# MSP-EXP430F5529_2_2.net
KiCad netlist of a schematic drawn in EAGLE
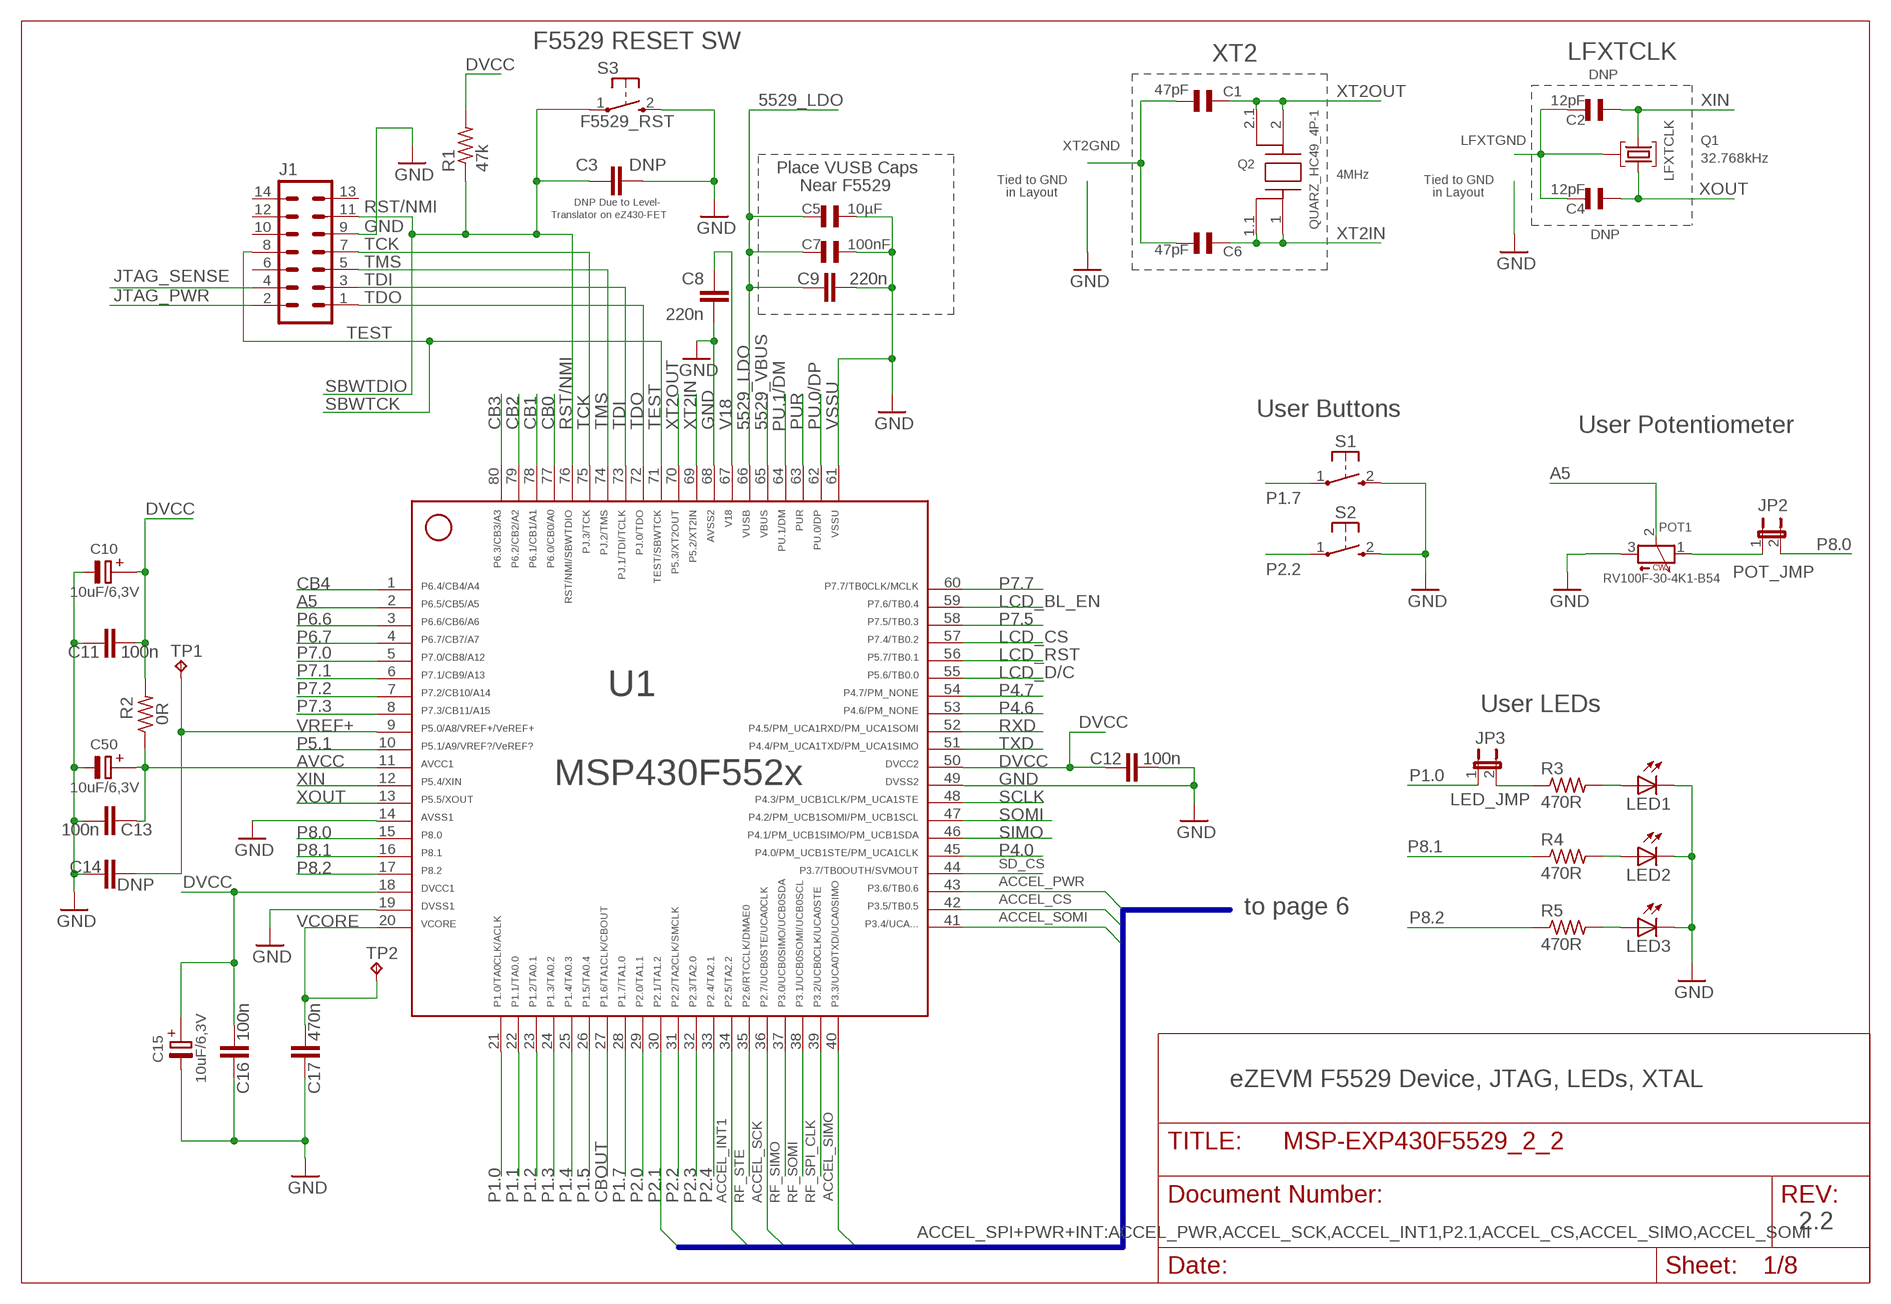
[diagram p0: schematic, sheet 1]
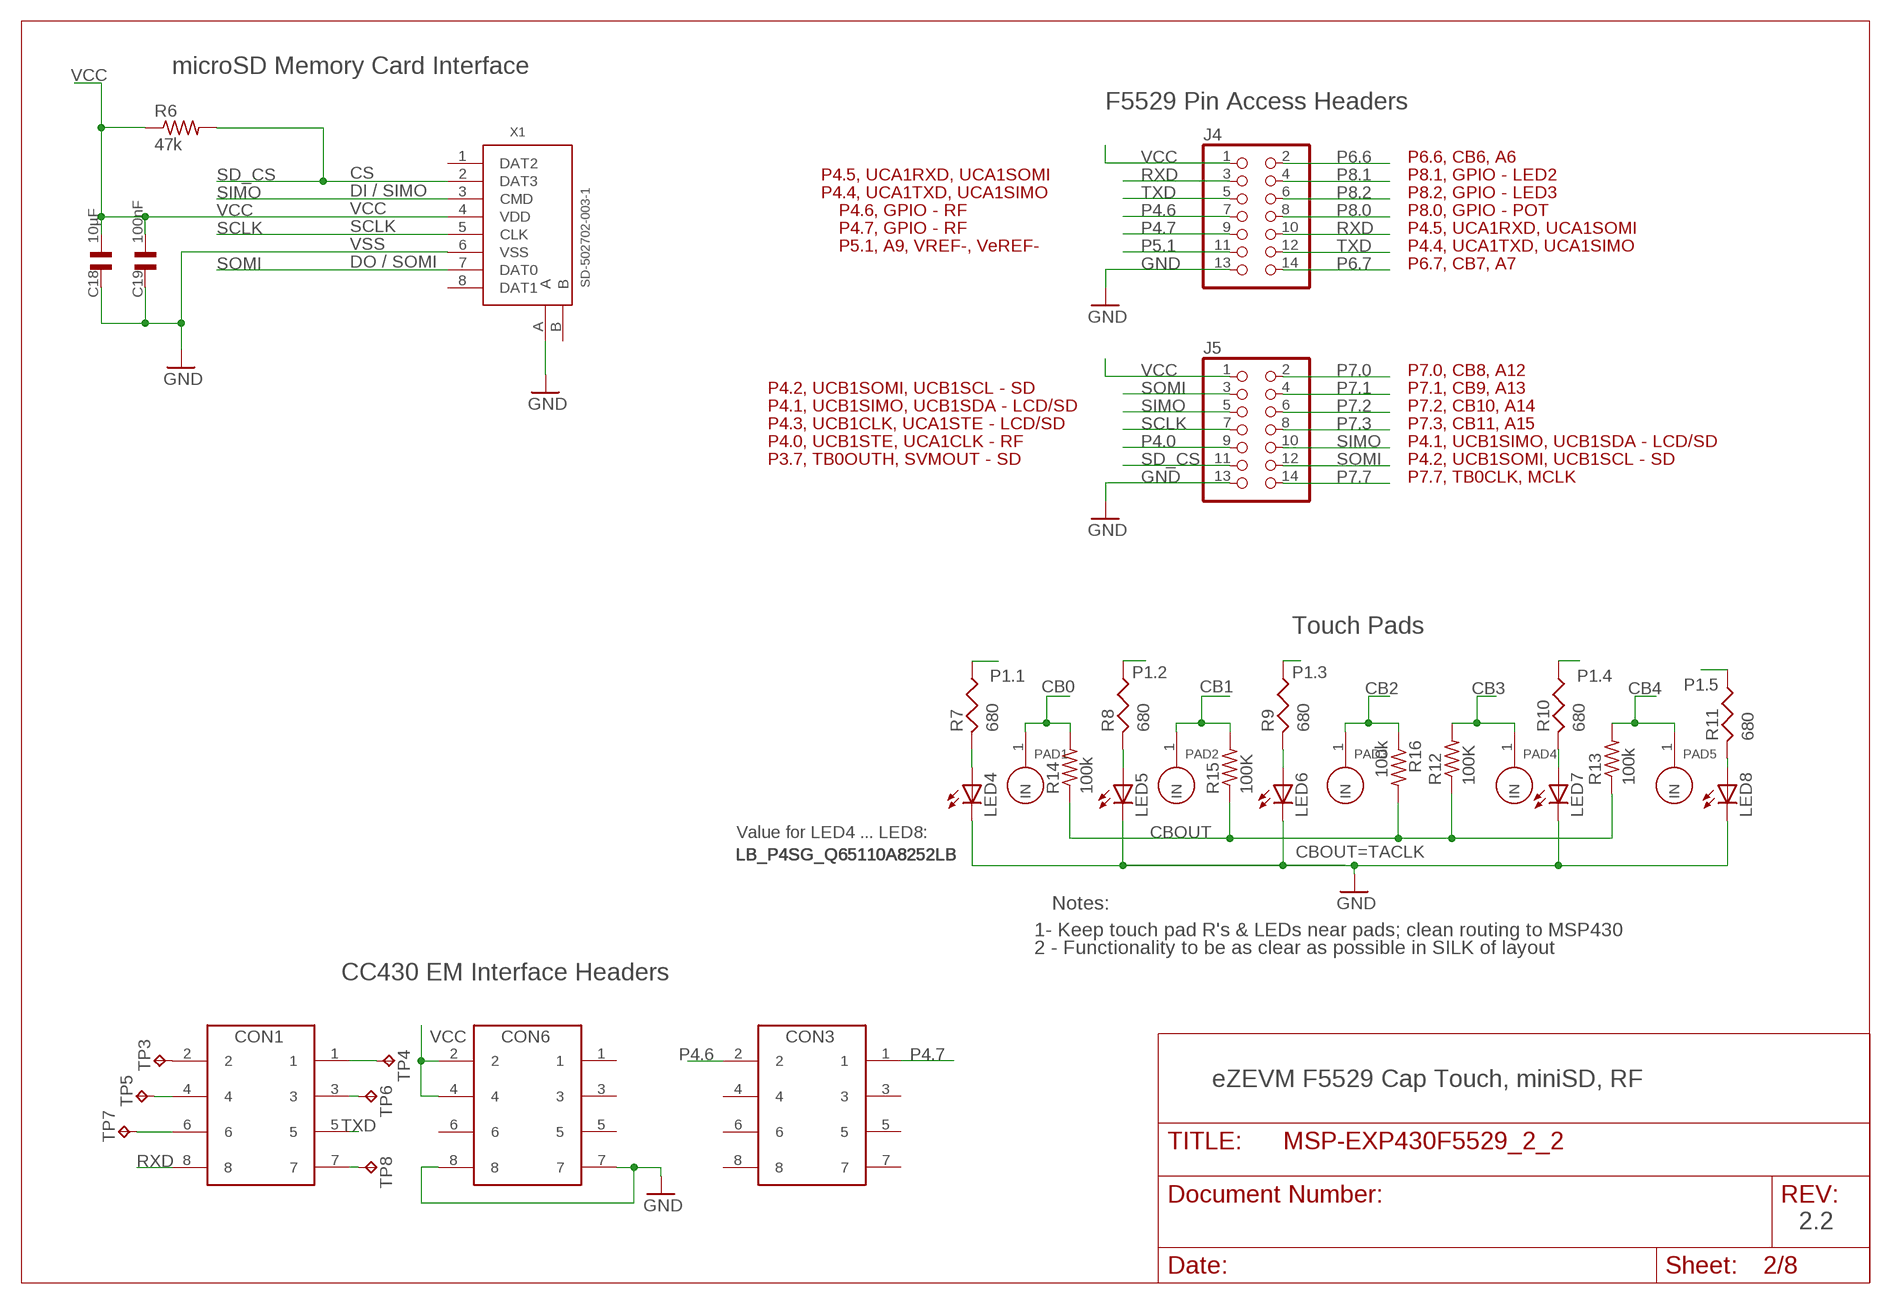
[diagram p1: schematic, sheet 2]
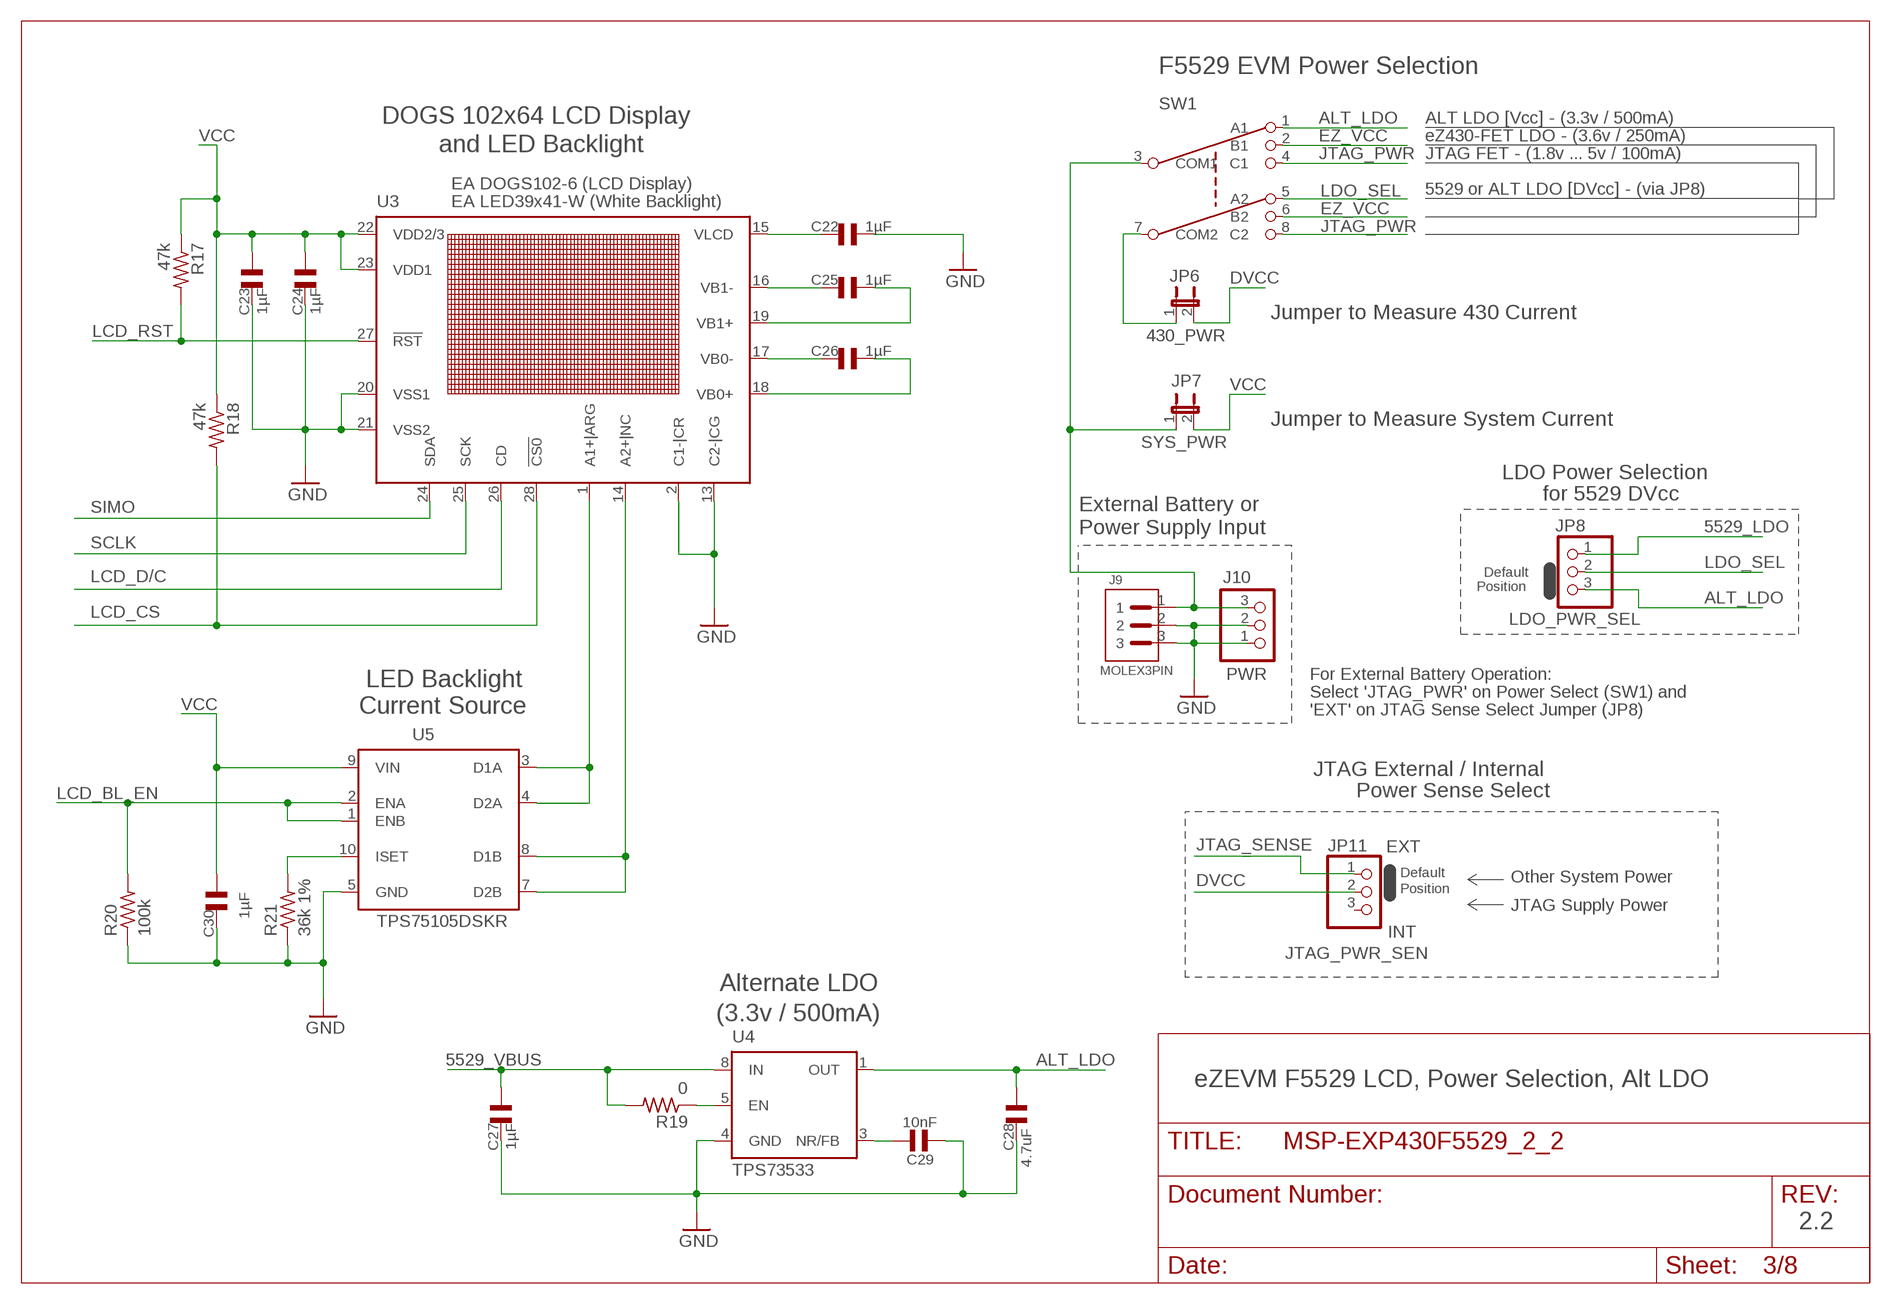
[diagram p2: schematic, sheet 3]
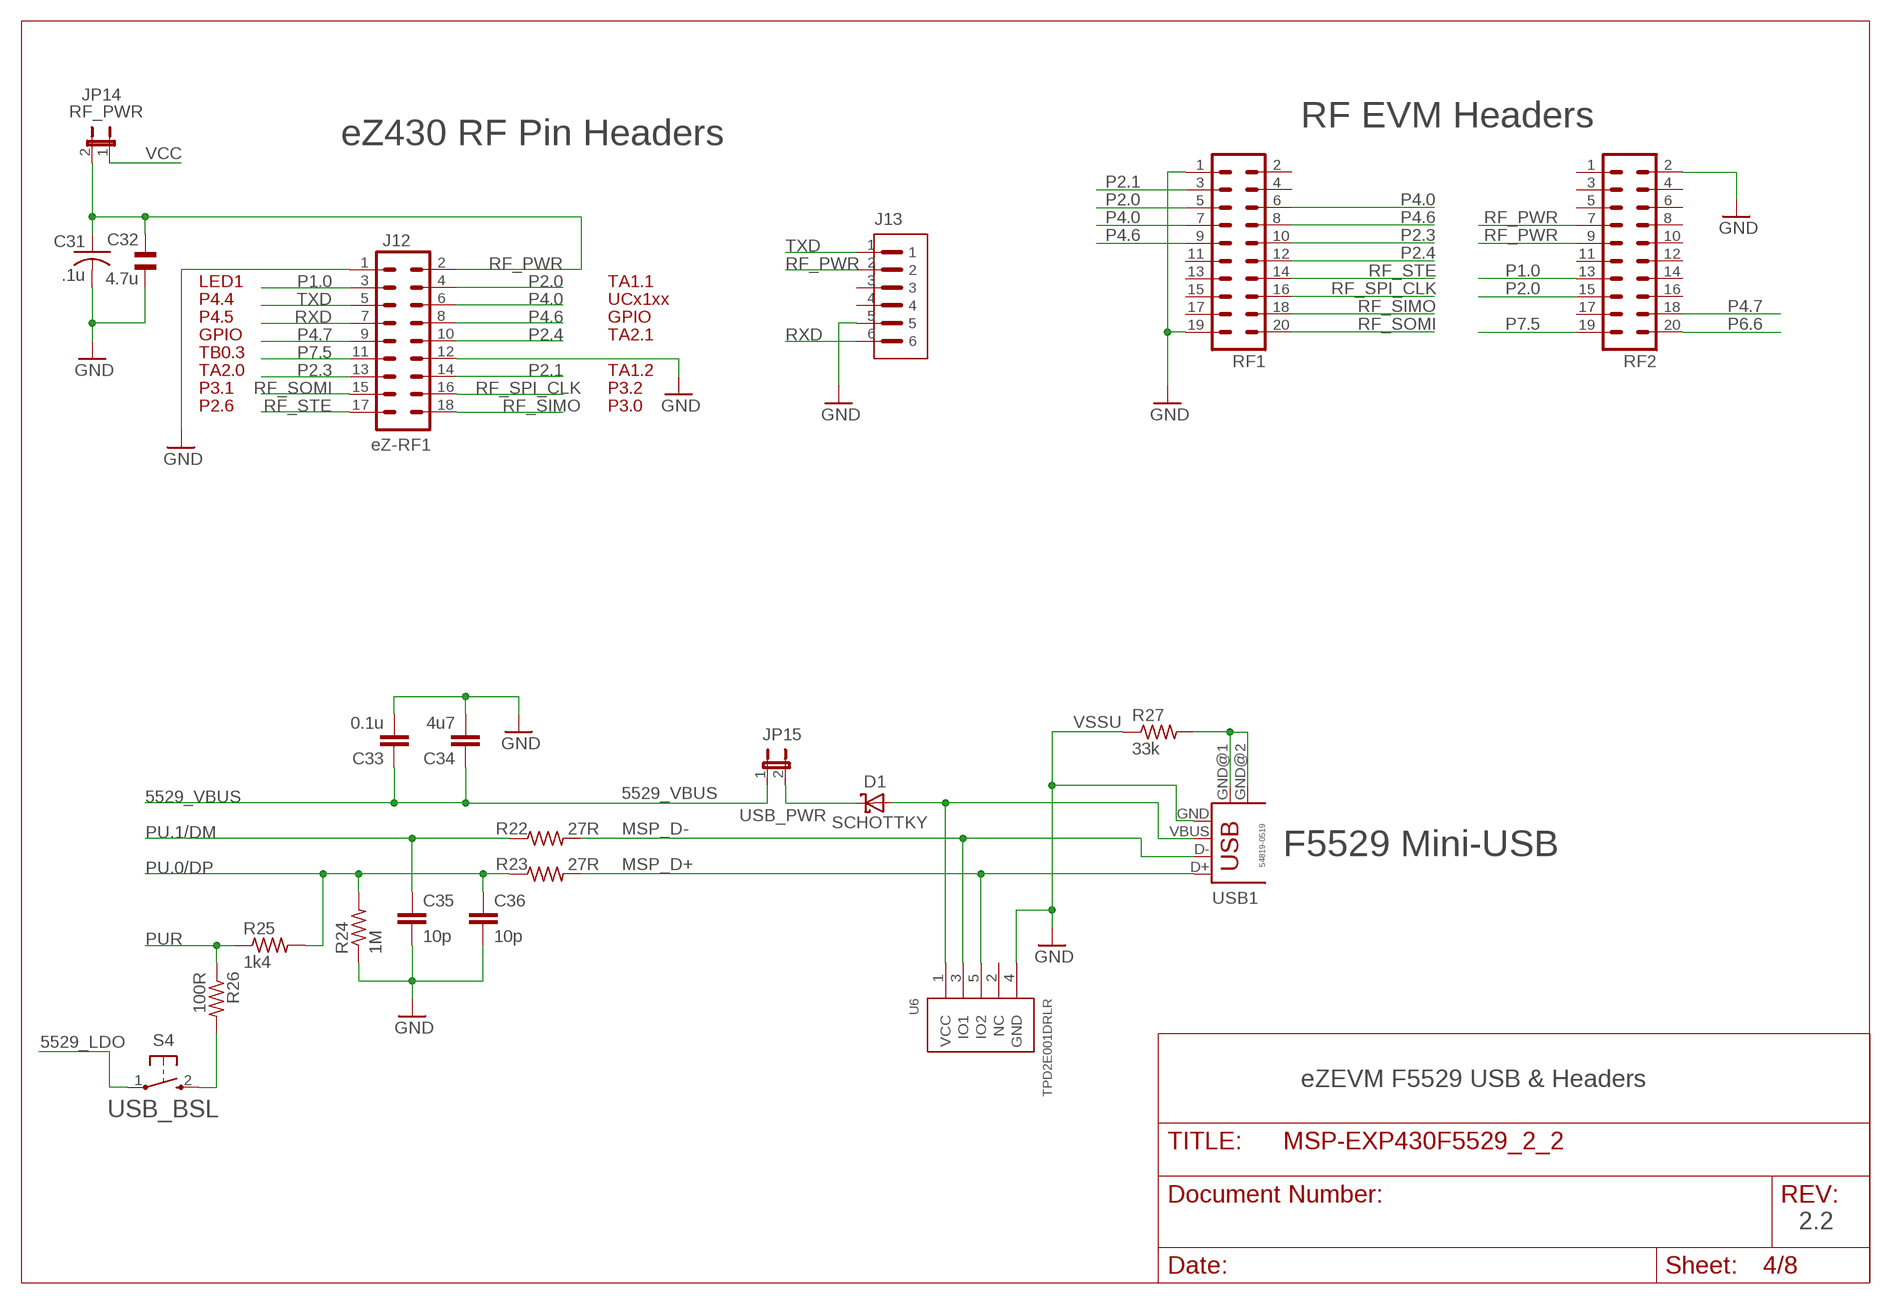
[diagram p3: schematic, sheet 4]
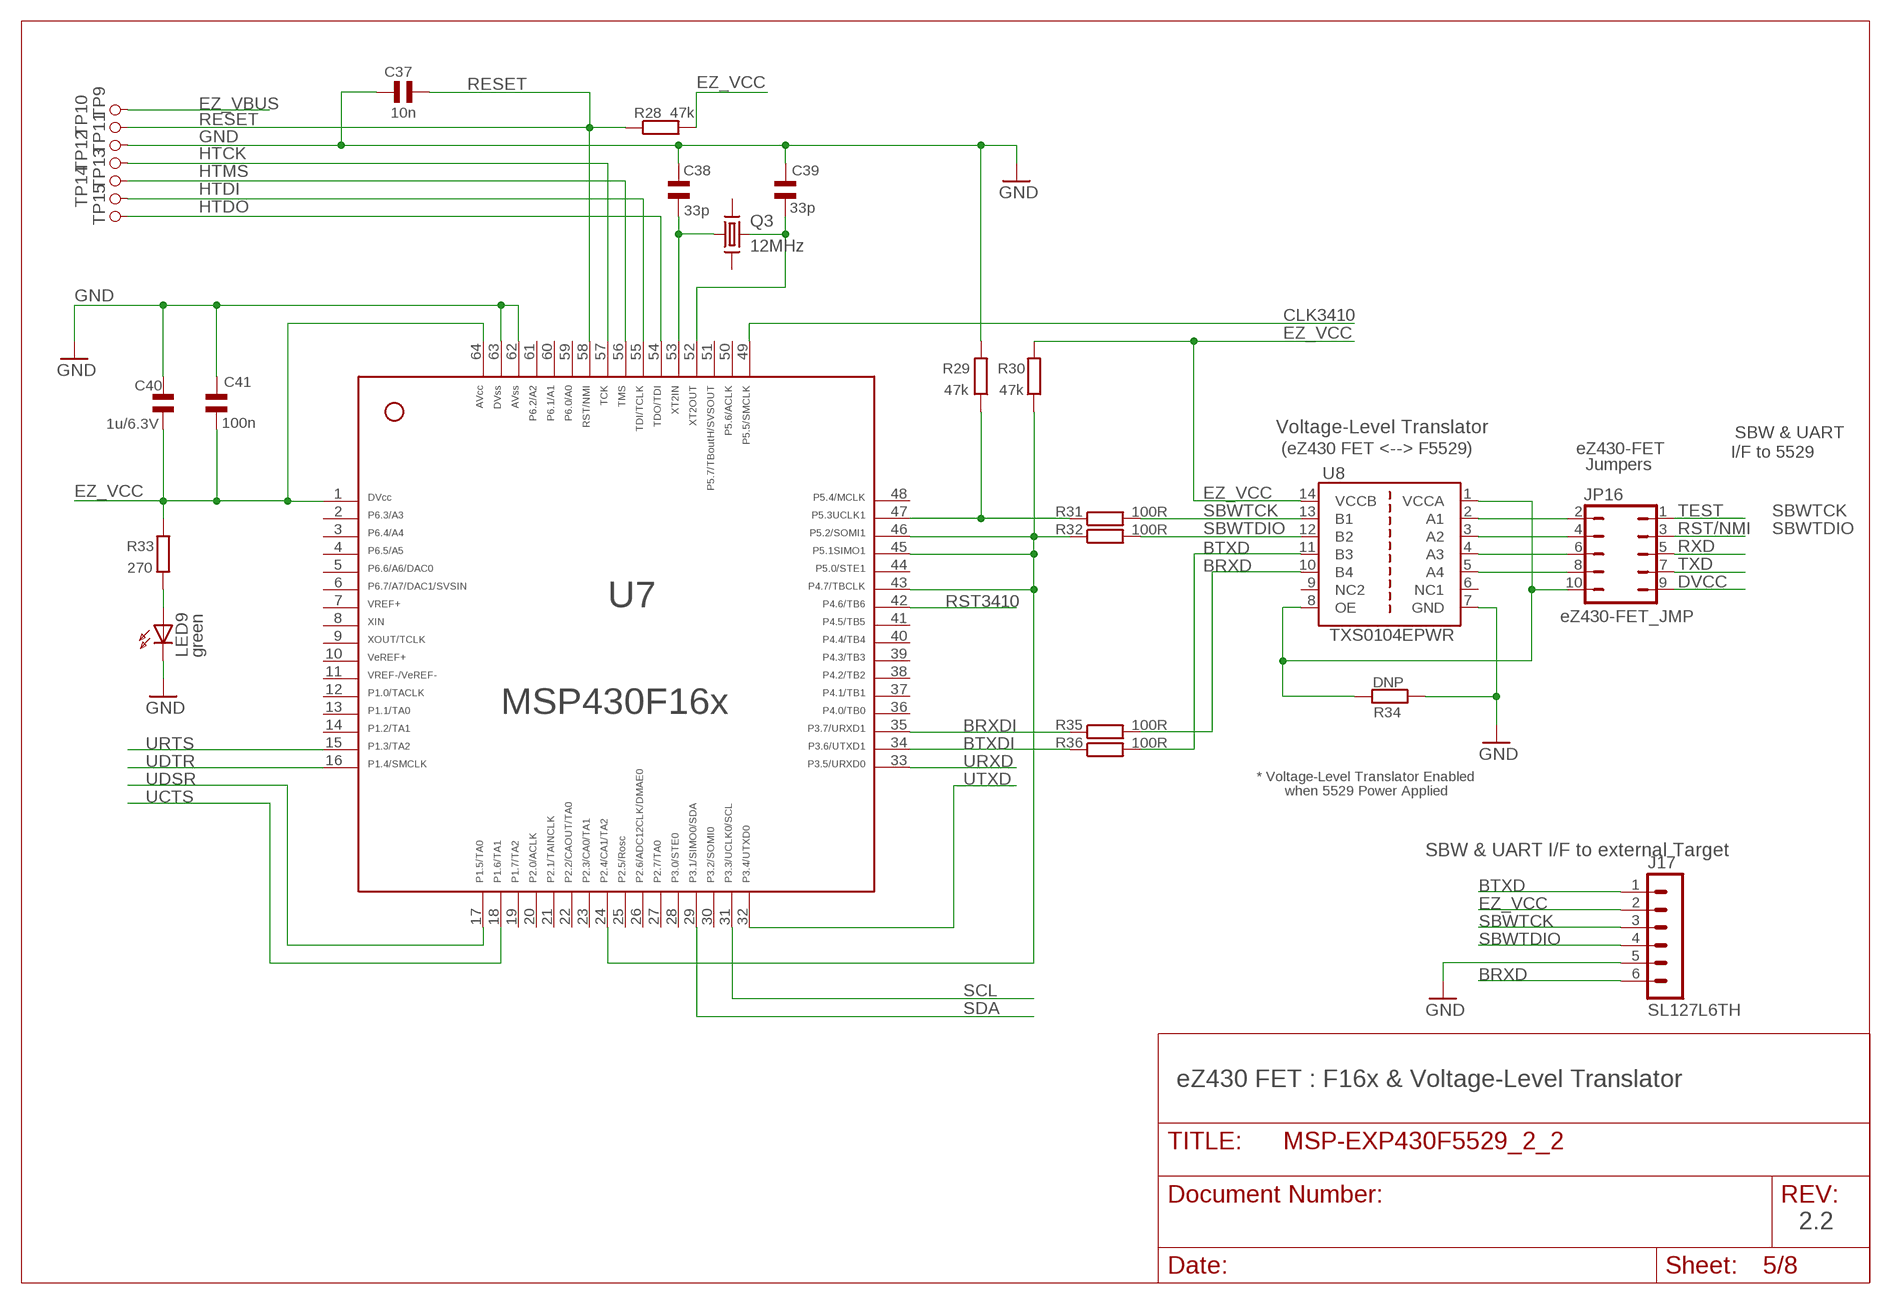
[diagram p4: schematic, sheet 5]
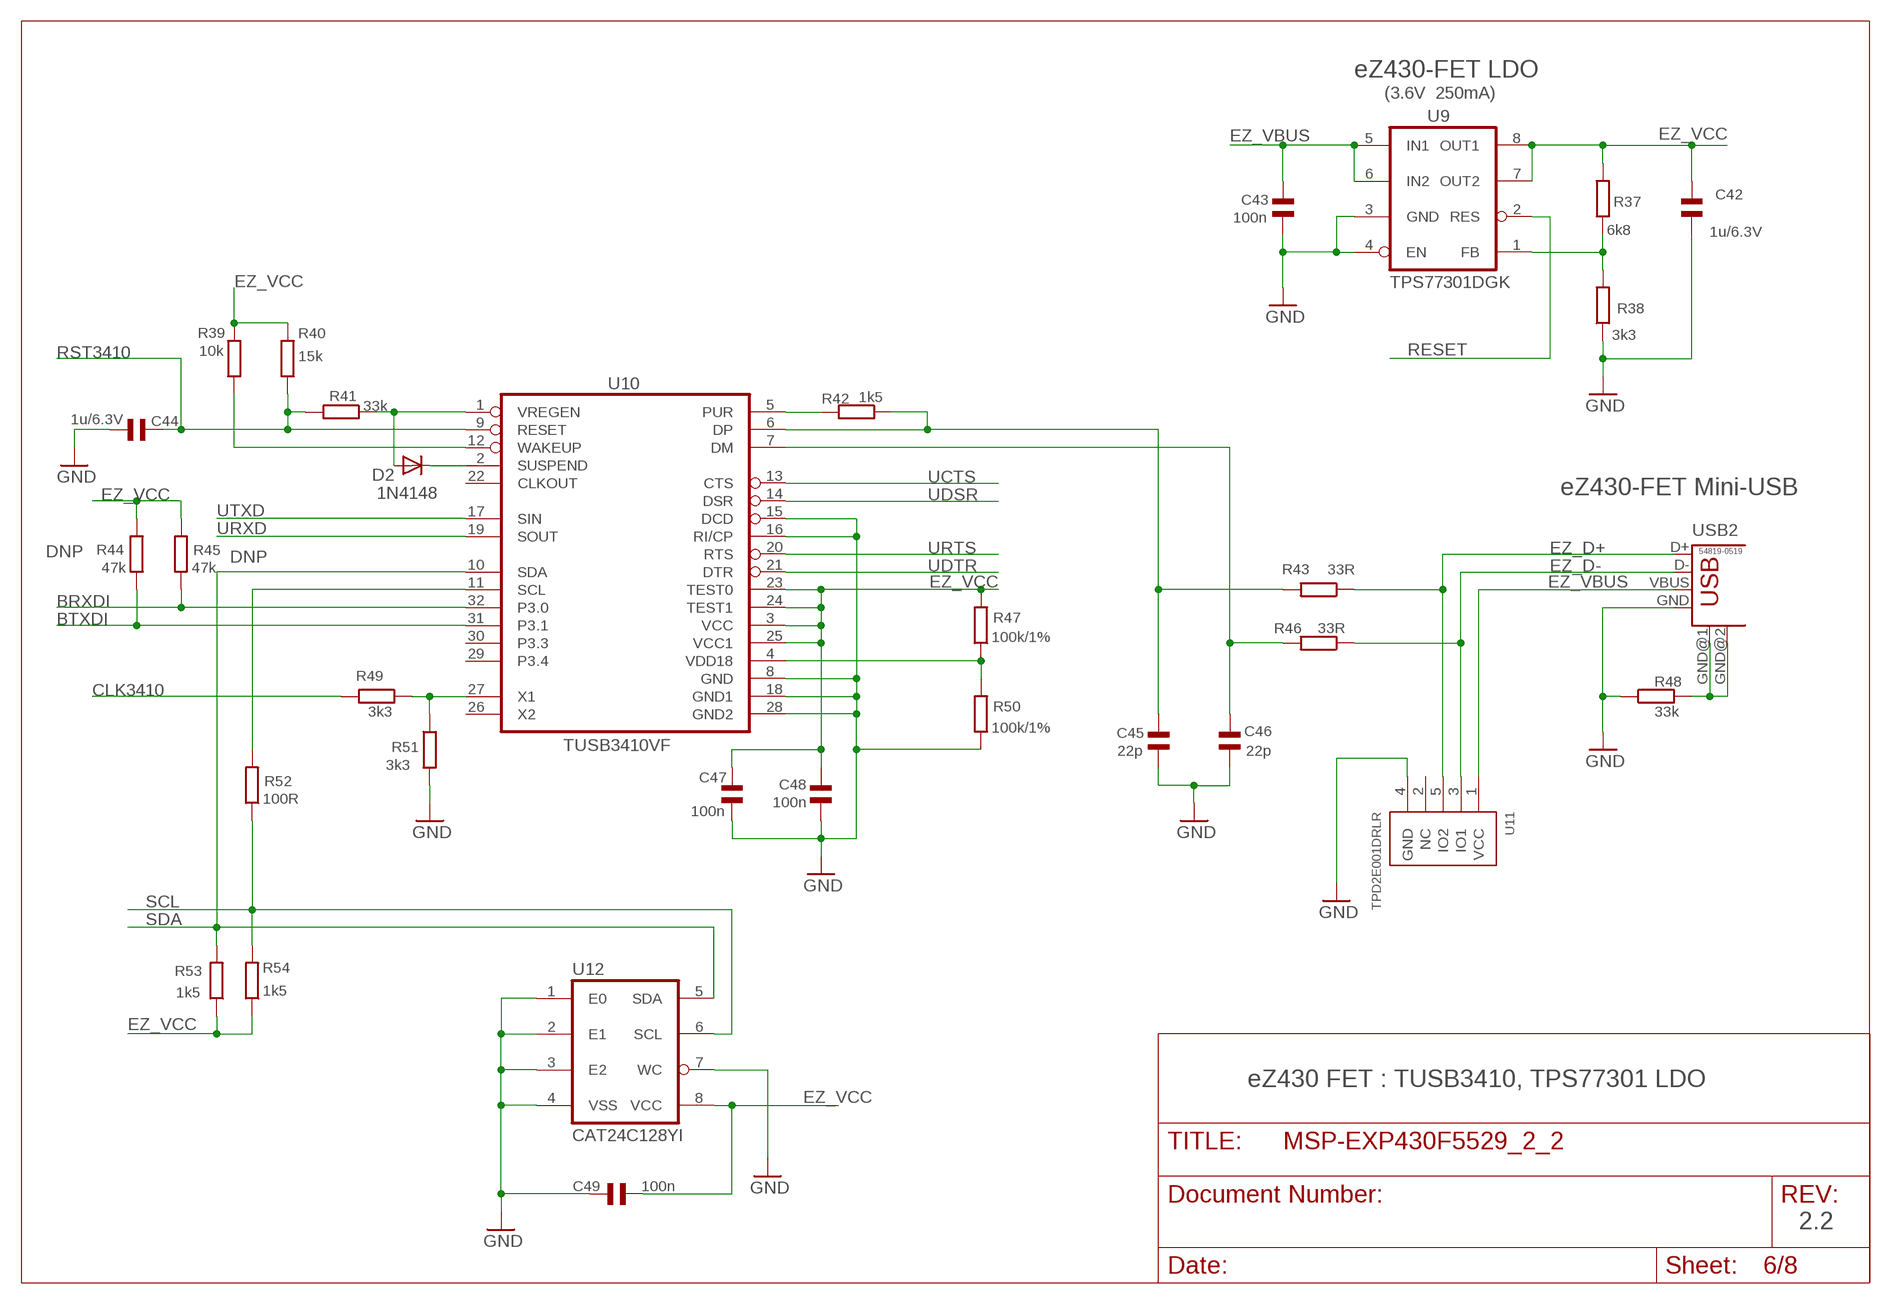
[diagram p5: schematic, sheet 6]
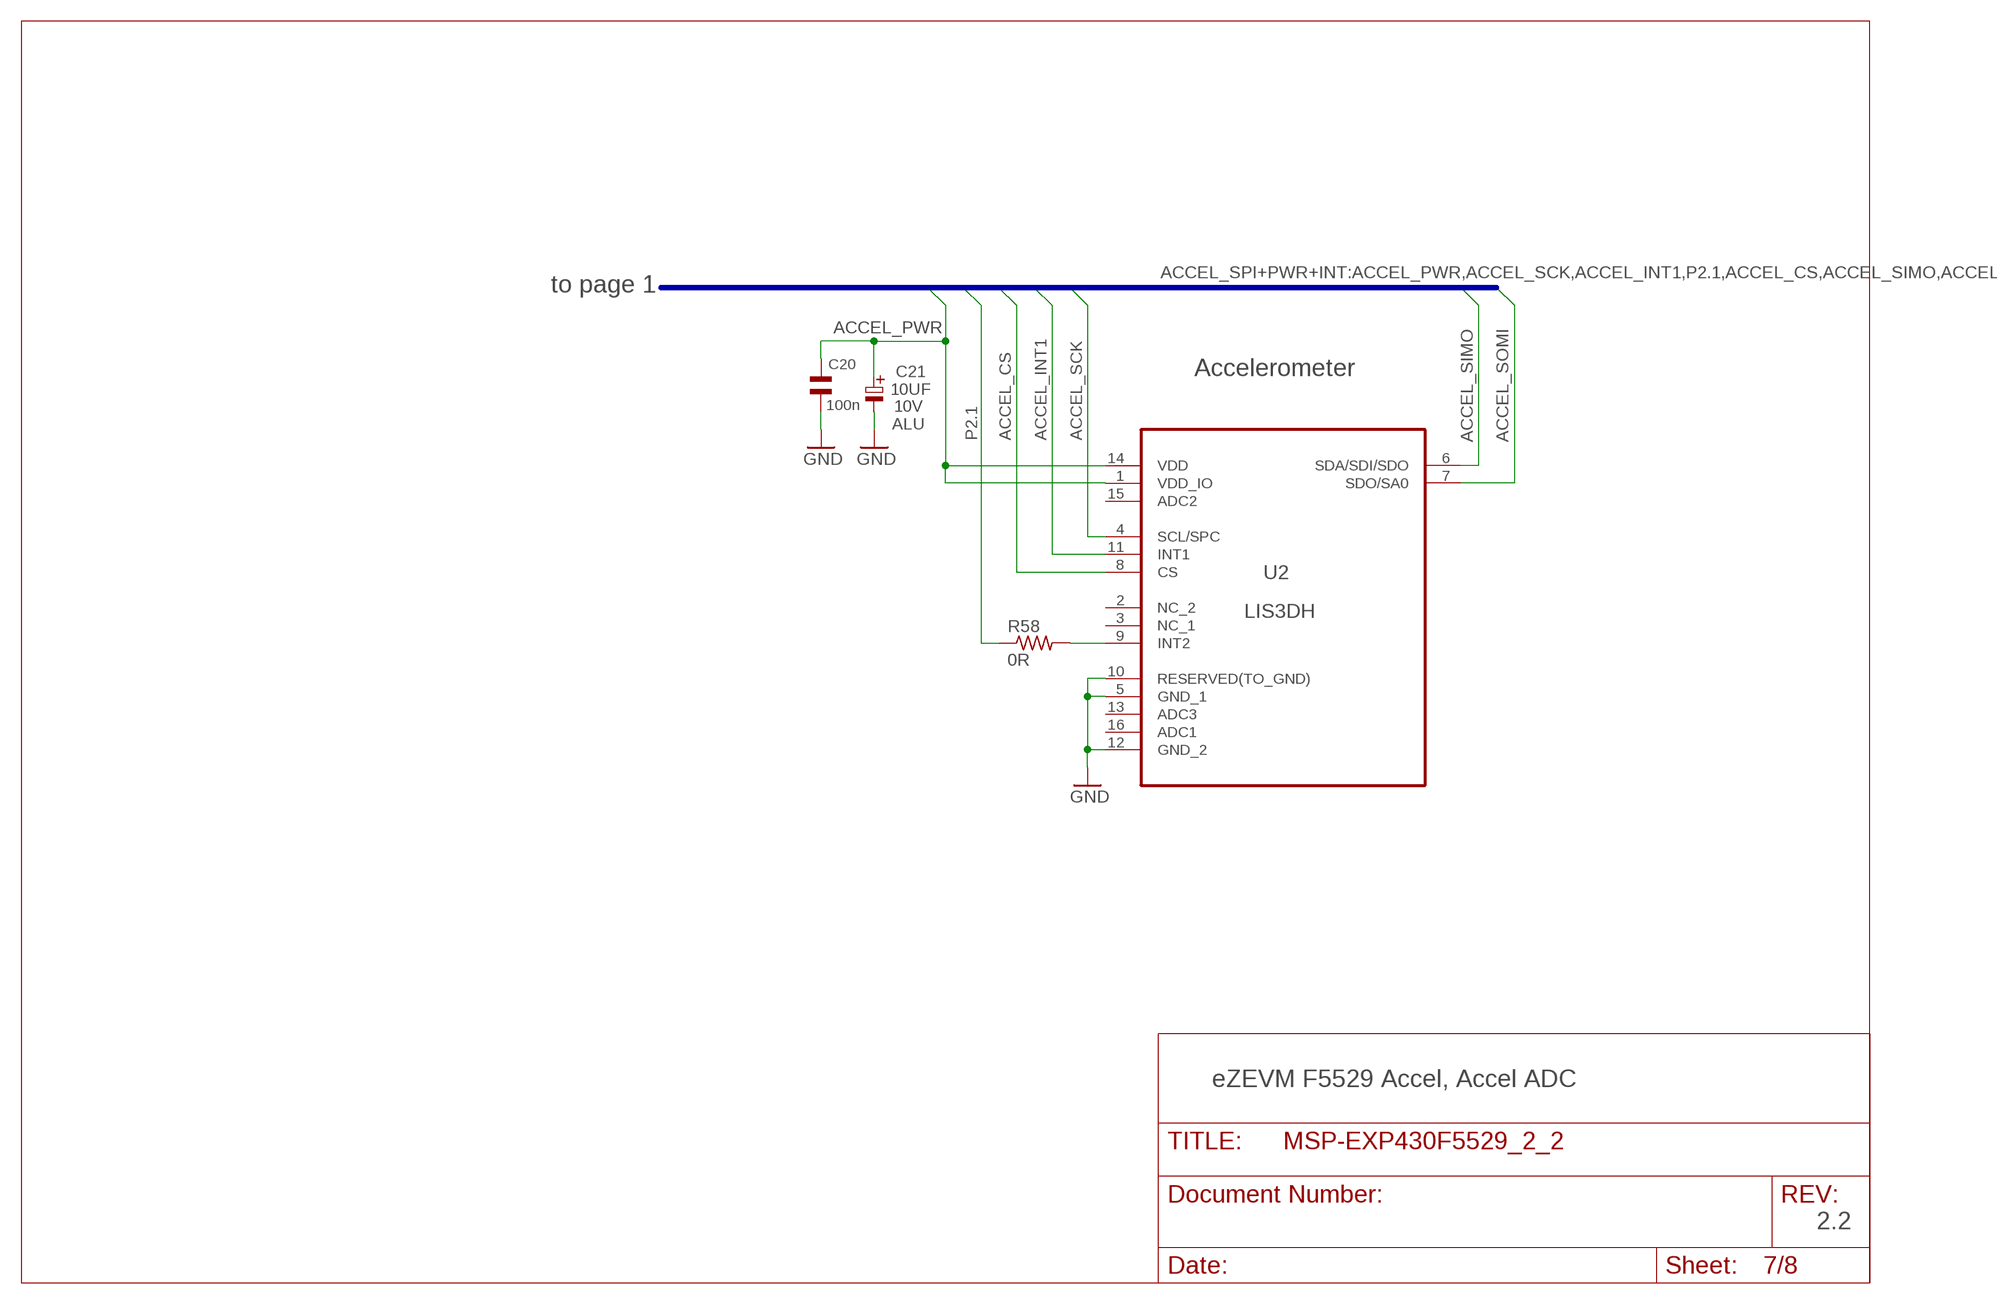
[diagram p6: schematic, sheet 7]
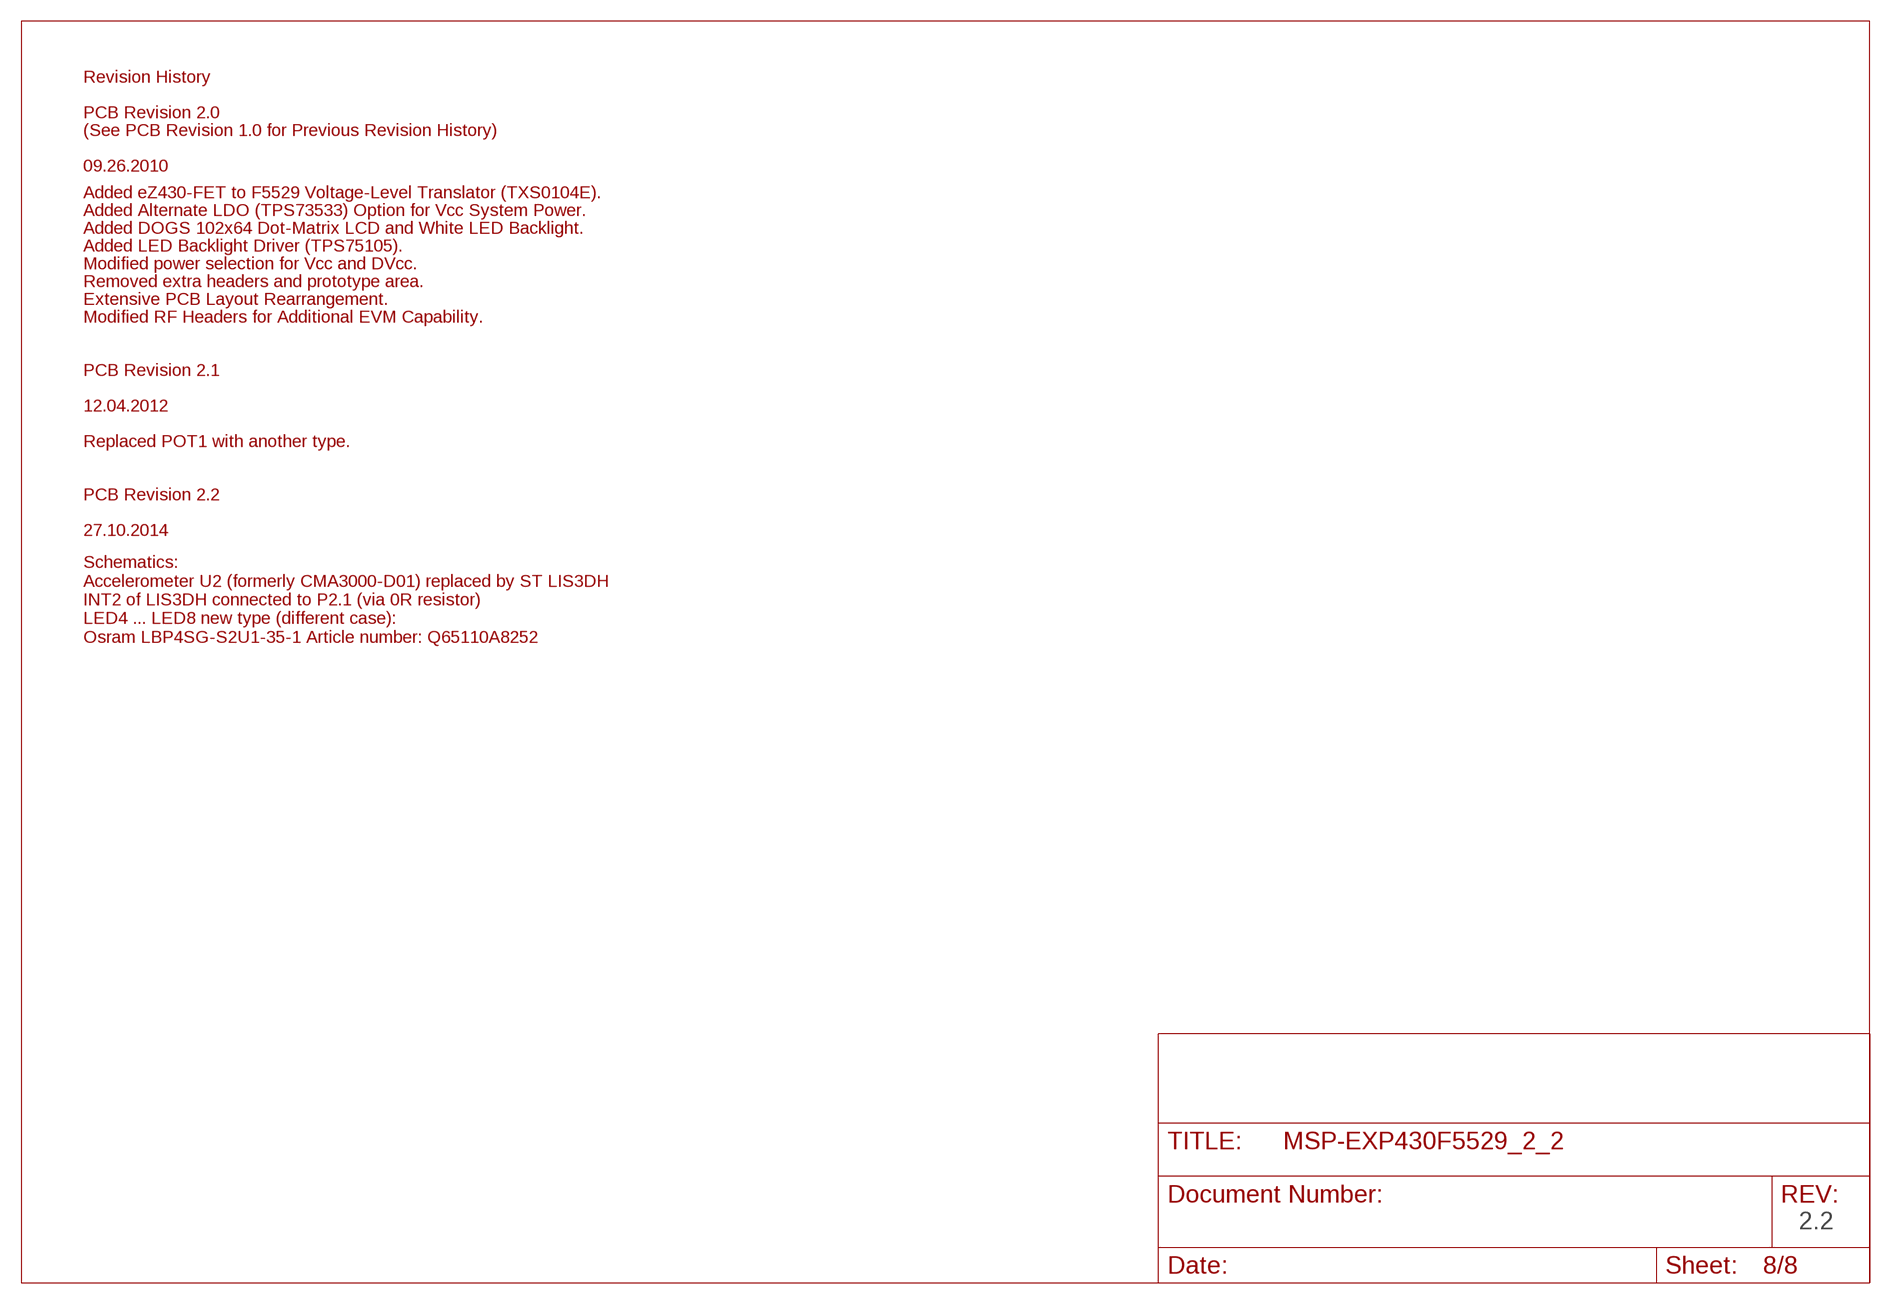
[diagram p7: schematic, sheet 8]

(export (version "E")
  (design (tool "Eeschema 10.0.6"))
  (components
    (comp (ref "C42")
      (value "1u/6.3V")
      (footprint "eagle-import:0603")
      (libsource (lib "eagle-import") (part "C_SMD0603"))
    )
    (comp (ref "C43")
      (value "100n")
      (footprint "eagle-import:0402")
      (libsource (lib "eagle-import") (part "C_SMD0402"))
    )
    (comp (ref "C44")
      (value "1u/6.3V")
      (footprint "eagle-import:0603")
      (libsource (lib "eagle-import") (part "C_SMD0603"))
    )
    (comp (ref "C45")
      (value "22p")
      (footprint "eagle-import:0402")
      (libsource (lib "eagle-import") (part "C_SMD0402"))
    )
    (comp (ref "C46")
      (value "22p")
      (footprint "eagle-import:0402")
      (libsource (lib "eagle-import") (part "C_SMD0402"))
    )
    (comp (ref "C47")
      (value "100n")
      (footprint "eagle-import:0402")
      (libsource (lib "eagle-import") (part "C_SMD0402"))
    )
    (comp (ref "C48")
      (value "100n")
      (footprint "eagle-import:0402")
      (libsource (lib "eagle-import") (part "C_SMD0402"))
    )
    (comp (ref "C49")
      (value "100n")
      (footprint "eagle-import:0402")
      (libsource (lib "eagle-import") (part "C_SMD0402"))
    )
    (comp (ref "D2")
      (value "1N4148")
      (footprint "eagle-import:SOD110-R")
      (libsource (lib "eagle-import") (part "DIODE-SOD110-R"))
    )
    (comp (ref "R37")
      (value "6k8")
      (footprint "eagle-import:0402")
      (libsource (lib "eagle-import") (part "R_SMDR0402"))
    )
    (comp (ref "R38")
      (value "3k3")
      (footprint "eagle-import:0402")
      (libsource (lib "eagle-import") (part "R_SMDR0402"))
    )
    (comp (ref "R39")
      (value "10k")
      (footprint "eagle-import:0402")
      (libsource (lib "eagle-import") (part "R_SMDR0402"))
    )
    (comp (ref "R40")
      (value "15k")
      (footprint "eagle-import:0402")
      (libsource (lib "eagle-import") (part "R_SMDR0402"))
    )
    (comp (ref "R41")
      (value "33k")
      (footprint "eagle-import:0402")
      (libsource (lib "eagle-import") (part "R_SMDR0402"))
    )
    (comp (ref "R42")
      (value "1k5")
      (footprint "eagle-import:0402")
      (libsource (lib "eagle-import") (part "R_SMDR0402"))
    )
    (comp (ref "R43")
      (value "33R")
      (footprint "eagle-import:0402")
      (libsource (lib "eagle-import") (part "R_SMDR0402"))
    )
    (comp (ref "R44")
      (value "47k")
      (footprint "eagle-import:0402")
      (libsource (lib "eagle-import") (part "R_SMDR0402"))
    )
    (comp (ref "R45")
      (value "47k")
      (footprint "eagle-import:0402")
      (libsource (lib "eagle-import") (part "R_SMDR0402"))
    )
    (comp (ref "R46")
      (value "33R")
      (footprint "eagle-import:0402")
      (libsource (lib "eagle-import") (part "R_SMDR0402"))
    )
    (comp (ref "R47")
      (value "100k/1%")
      (footprint "eagle-import:0402")
      (libsource (lib "eagle-import") (part "R_SMDR0402"))
    )
    (comp (ref "R48")
      (value "33k")
      (footprint "eagle-import:0402")
      (libsource (lib "eagle-import") (part "R_SMDR0402"))
    )
    (comp (ref "R49")
      (value "3k3")
      (footprint "eagle-import:0402")
      (libsource (lib "eagle-import") (part "R_SMDR0402"))
    )
    (comp (ref "R50")
      (value "100k/1%")
      (footprint "eagle-import:0402")
      (libsource (lib "eagle-import") (part "R_SMDR0402"))
    )
    (comp (ref "R51")
      (value "3k3")
      (footprint "eagle-import:0402")
      (libsource (lib "eagle-import") (part "R_SMDR0402"))
    )
    (comp (ref "R52")
      (value "100R")
      (footprint "eagle-import:0402")
      (libsource (lib "eagle-import") (part "R_SMDR0402"))
    )
    (comp (ref "R53")
      (value "1k5")
      (footprint "eagle-import:0402")
      (libsource (lib "eagle-import") (part "R_SMDR0402"))
    )
    (comp (ref "R54")
      (value "1k5")
      (footprint "eagle-import:0402")
      (libsource (lib "eagle-import") (part "R_SMDR0402"))
    )
    (comp (ref "U9")
      (value "TPS77301DGK")
      (footprint "eagle-import:MSOP8")
      (libsource (lib "eagle-import") (part "TPS773XX"))
    )
    (comp (ref "U10")
      (value "TUSB3410VF")
      (footprint "eagle-import:QFP32")
      (libsource (lib "eagle-import") (part "TUSB3410"))
    )
    (comp (ref "U11")
      (value "TPD2E001DRLR")
      (footprint "eagle-import:TPD2E001-DRL")
      (libsource (lib "eagle-import") (part "TPD2E001"))
    )
    (comp (ref "U12")
      (value "CAT24C128YI")
      (footprint "eagle-import:USBFET_TSSOP8")
      (libsource (lib "eagle-import") (part "USBFET_M24XXX"))
    )
    (comp (ref "USB2")
      (value "eZ430-FET Mini-USB")
      (footprint "eagle-import:USB-MB-H")
      (libsource (lib "eagle-import") (part "USB-MB-H"))
    )
    (comp (ref "C1")
      (value "47pF")
      (footprint "eagle-import:CSMD0805")
      (libsource (lib "eagle-import") (part "CSMD0805"))
    )
    (comp (ref "C2")
      (value "12pF")
      (footprint "eagle-import:CSMD0805")
      (libsource (lib "eagle-import") (part "CSMD0805"))
    )
    (comp (ref "C3")
      (value "DNP")
      (footprint "eagle-import:C0603")
      (libsource (lib "eagle-import") (part "C-EUC0603"))
    )
    (comp (ref "C4")
      (value "12pF")
      (footprint "eagle-import:CSMD0805")
      (libsource (lib "eagle-import") (part "CSMD0805"))
    )
    (comp (ref "C5")
      (value "10µF")
      (footprint "eagle-import:CSMD0805")
      (libsource (lib "eagle-import") (part "CSMD0805"))
    )
    (comp (ref "C6")
      (value "47pF")
      (footprint "eagle-import:CSMD0805")
      (libsource (lib "eagle-import") (part "CSMD0805"))
    )
    (comp (ref "C7")
      (value "100nF")
      (footprint "eagle-import:CSMD0805")
      (libsource (lib "eagle-import") (part "CSMD0805"))
    )
    (comp (ref "C8")
      (value "220n")
      (footprint "eagle-import:C0603")
      (libsource (lib "eagle-import") (part "C-EUC0603"))
    )
    (comp (ref "C9")
      (value "220n")
      (footprint "eagle-import:C0603")
      (libsource (lib "eagle-import") (part "C-EUC0603"))
    )
    (comp (ref "C10")
      (value "10uF/6,3V")
      (footprint "eagle-import:1210ELKO")
      (libsource (lib "eagle-import") (part "ELKO_1210"))
    )
    (comp (ref "C11")
      (value "100n")
      (footprint "eagle-import:C0603")
      (libsource (lib "eagle-import") (part "C-EUC0603"))
    )
    (comp (ref "C12")
      (value "100n")
      (footprint "eagle-import:C0805")
      (libsource (lib "eagle-import") (part "C-EUC0805"))
    )
    (comp (ref "C13")
      (value "100n")
      (footprint "eagle-import:C0805")
      (libsource (lib "eagle-import") (part "C-EUC0805"))
    )
    (comp (ref "C14")
      (value "DNP")
      (footprint "eagle-import:C0603")
      (libsource (lib "eagle-import") (part "C-EUC0603"))
    )
    (comp (ref "C15")
      (value "10uF/6,3V")
      (footprint "eagle-import:1210ELKO")
      (libsource (lib "eagle-import") (part "ELKO_1210"))
    )
    (comp (ref "C16")
      (value "100n")
      (footprint "eagle-import:C0805")
      (libsource (lib "eagle-import") (part "C-EUC0805"))
    )
    (comp (ref "C17")
      (value "470n")
      (footprint "eagle-import:C0805")
      (libsource (lib "eagle-import") (part "C-EUC0805"))
    )
    (comp (ref "C50")
      (value "10uF/6,3V")
      (footprint "eagle-import:1210ELKO")
      (libsource (lib "eagle-import") (part "ELKO_1210"))
    )
    (comp (ref "J1")
      (value "ML14")
      (footprint "eagle-import:ML14")
      (libsource (lib "eagle-import") (part "ML14"))
    )
    (comp (ref "JP2")
      (value "POT_JMP")
      (footprint "eagle-import:JP1S")
      (libsource (lib "eagle-import") (part "JP1E{backslash}SMALL_PIN"))
    )
    (comp (ref "JP3")
      (value "LED_JMP")
      (footprint "eagle-import:JP1S")
      (libsource (lib "eagle-import") (part "JP1E{backslash}SMALL_PIN"))
    )
    (comp (ref "LED1")
      (value "LEDCHIPLED_0603")
      (footprint "eagle-import:CHIPLED_0603")
      (libsource (lib "eagle-import") (part "LEDCHIPLED_0603"))
    )
    (comp (ref "LED2")
      (value "LEDCHIPLED_0603")
      (footprint "eagle-import:CHIPLED_0603")
      (libsource (lib "eagle-import") (part "LEDCHIPLED_0603"))
    )
    (comp (ref "LED3")
      (value "LEDCHIPLED_0603")
      (footprint "eagle-import:CHIPLED_0603")
      (libsource (lib "eagle-import") (part "LEDCHIPLED_0603"))
    )
    (comp (ref "POT1")
      (value "RV100F-30-4K1-B54")
      (footprint "eagle-import:TW-700171")
      (libsource (lib "eagle-import") (part "RV100F-30-4K1-B54"))
    )
    (comp (ref "Q1")
      (value "32.768kHz")
      (footprint "eagle-import:F20XX_PIR_DEMO_&_EVAL_CMJ206T")
      (libsource (lib "eagle-import") (part "F20XX_PIR_DEMO_&_EVAL_CM200T"))
    )
    (comp (ref "Q2")
      (value "QUARZ_HC49_4P-1")
      (footprint "eagle-import:QUARZ_HC49_4P")
      (libsource (lib "eagle-import") (part "QUARZ_HC49_4P-1"))
    )
    (comp (ref "R1")
      (value "47k")
      (footprint "eagle-import:R0603")
      (libsource (lib "eagle-import") (part "rcl_R-US_R0603"))
    )
    (comp (ref "R2")
      (value "0R")
      (footprint "eagle-import:R0603")
      (libsource (lib "eagle-import") (part "rcl_R-US_R0603"))
    )
    (comp (ref "R3")
      (value "470R")
      (footprint "eagle-import:R0603")
      (libsource (lib "eagle-import") (part "R-US_R0603"))
    )
    (comp (ref "R4")
      (value "470R")
      (footprint "eagle-import:R0603")
      (libsource (lib "eagle-import") (part "R-US_R0603"))
    )
    (comp (ref "R5")
      (value "470R")
      (footprint "eagle-import:R0603")
      (libsource (lib "eagle-import") (part "R-US_R0603"))
    )
    (comp (ref "S1")
      (value "PB")
      (footprint "eagle-import:PBTH")
      (libsource (lib "eagle-import") (part "PB"))
    )
    (comp (ref "S2")
      (value "PB")
      (footprint "eagle-import:PBTH")
      (libsource (lib "eagle-import") (part "PB"))
    )
    (comp (ref "S3")
      (value "F5529_RST")
      (footprint "eagle-import:PBTH")
      (libsource (lib "eagle-import") (part "PB"))
    )
    (comp (ref "TP1") (value "TP") (footprint "eagle-import:TP") (libsource (lib "eagle-import") (part "TP")))
    (comp (ref "TP2") (value "TP") (footprint "eagle-import:TP") (libsource (lib "eagle-import") (part "TP")))
    (comp (ref "U1")
      (value "MSP430F5529IPNR")
      (footprint "eagle-import:PN80")
      (libsource (lib "eagle-import") (part "F552X---PN80"))
    )
    (comp (ref "C18")
      (value "10µF")
      (footprint "eagle-import:CSMD0805")
      (libsource (lib "eagle-import") (part "CSMD0805"))
    )
    (comp (ref "C19")
      (value "100nF")
      (footprint "eagle-import:CSMD0805")
      (libsource (lib "eagle-import") (part "CSMD0805"))
    )
    (comp (ref "CON1")
      (value "8PIN_SM_MA_HEADER")
      (footprint "eagle-import:8PIN_SM_MA_HEADER")
      (libsource (lib "eagle-import") (part "8PIN_SM_MA_HEADER"))
    )
    (comp (ref "CON2")
      (value "8PIN_SM_MA_HEADER")
      (footprint "eagle-import:8PIN_SM_MA_HEADER")
      (libsource (lib "eagle-import") (part "8PIN_SM_MA_HEADER"))
    )
    (comp (ref "CON3")
      (value "8PIN_SM_MA_HEADER")
      (footprint "eagle-import:8PIN_SM_MA_HEADER")
      (libsource (lib "eagle-import") (part "8PIN_SM_MA_HEADER"))
    )
    (comp (ref "J4")
      (value "PINHD-2X7")
      (footprint "eagle-import:2X07")
      (libsource (lib "eagle-import") (part "PINHD-2X7"))
    )
    (comp (ref "J5")
      (value "PINHD-2X7")
      (footprint "eagle-import:2X07")
      (libsource (lib "eagle-import") (part "PINHD-2X7"))
    )
    (comp (ref "LED4")
      (value "LB_P4SG_Q65110A8252LB")
      (footprint "eagle-import:LB_P4SG_Q65110A8252")
      (fields (field (name "MANUFACTURER") "Osram") (field (name "MPN") "LBP4SG-bbbb-35-1 (Q65110A8252)"))
      (libsource (lib "eagle-import") (part "LB_P4SG_Q65110A8252LB"))
    )
    (comp (ref "LED5")
      (value "LB_P4SG_Q65110A8252LB")
      (footprint "eagle-import:LB_P4SG_Q65110A8252")
      (fields (field (name "MANUFACTURER") "Osram") (field (name "MPN") "LBP4SG-bbbb-35-1 (Q65110A8252)"))
      (libsource (lib "eagle-import") (part "LB_P4SG_Q65110A8252LB"))
    )
    (comp (ref "LED6")
      (value "LB_P4SG_Q65110A8252LB")
      (footprint "eagle-import:LB_P4SG_Q65110A8252")
      (fields (field (name "MANUFACTURER") "Osram") (field (name "MPN") "LBP4SG-bbbb-35-1 (Q65110A8252)"))
      (libsource (lib "eagle-import") (part "LB_P4SG_Q65110A8252LB"))
    )
    (comp (ref "LED7")
      (value "LB_P4SG_Q65110A8252LB")
      (footprint "eagle-import:LB_P4SG_Q65110A8252")
      (fields (field (name "MANUFACTURER") "Osram") (field (name "MPN") "LBP4SG-bbbb-35-1 (Q65110A8252)"))
      (libsource (lib "eagle-import") (part "LB_P4SG_Q65110A8252LB"))
    )
    (comp (ref "LED8")
      (value "LB_P4SG_Q65110A8252LB")
      (footprint "eagle-import:LB_P4SG_Q65110A8252")
      (fields (field (name "MANUFACTURER") "Osram") (field (name "MPN") "LBP4SG-bbbb-35-1 (Q65110A8252)"))
      (libsource (lib "eagle-import") (part "LB_P4SG_Q65110A8252LB"))
    )
    (comp (ref "PAD1")
      (value "TPAD_TOPLB_P4SG")
      (footprint "eagle-import:PAD_10X10_LB_P4SG")
      (libsource (lib "eagle-import") (part "TPAD_TOPLB_P4SG"))
    )
    (comp (ref "PAD2")
      (value "TPAD_TOPLB_P4SG")
      (footprint "eagle-import:PAD_10X10_LB_P4SG")
      (libsource (lib "eagle-import") (part "TPAD_TOPLB_P4SG"))
    )
    (comp (ref "PAD3")
      (value "TPAD_TOPLB_P4SG")
      (footprint "eagle-import:PAD_10X10_LB_P4SG")
      (libsource (lib "eagle-import") (part "TPAD_TOPLB_P4SG"))
    )
    (comp (ref "PAD4")
      (value "TPAD_TOPLB_P4SG")
      (footprint "eagle-import:PAD_10X10_LB_P4SG")
      (libsource (lib "eagle-import") (part "TPAD_TOPLB_P4SG"))
    )
    (comp (ref "PAD5")
      (value "TPAD_TOPLB_P4SG")
      (footprint "eagle-import:PAD_10X10_LB_P4SG")
      (libsource (lib "eagle-import") (part "TPAD_TOPLB_P4SG"))
    )
    (comp (ref "R6")
      (value "47k")
      (footprint "eagle-import:R0603")
      (libsource (lib "eagle-import") (part "rcl_R-US_R0603"))
    )
    (comp (ref "R7")
      (value "680")
      (footprint "eagle-import:R0805")
      (libsource (lib "eagle-import") (part "RES0805"))
    )
    (comp (ref "R8")
      (value "680")
      (footprint "eagle-import:R0805")
      (libsource (lib "eagle-import") (part "RES0805"))
    )
    (comp (ref "R9")
      (value "680")
      (footprint "eagle-import:R0805")
      (libsource (lib "eagle-import") (part "RES0805"))
    )
    (comp (ref "R10")
      (value "680")
      (footprint "eagle-import:R0805")
      (libsource (lib "eagle-import") (part "RES0805"))
    )
    (comp (ref "R11")
      (value "680")
      (footprint "eagle-import:R0805")
      (libsource (lib "eagle-import") (part "RES0805"))
    )
    (comp (ref "R12")
      (value "100K")
      (footprint "eagle-import:R0603")
      (libsource (lib "eagle-import") (part "rcl_R-US_R0603"))
    )
    (comp (ref "R13")
      (value "100k")
      (footprint "eagle-import:R0603")
      (libsource (lib "eagle-import") (part "rcl_R-US_R0603"))
    )
    (comp (ref "R14")
      (value "100k")
      (footprint "eagle-import:R0603")
      (libsource (lib "eagle-import") (part "rcl_R-US_R0603"))
    )
    (comp (ref "R15")
      (value "100K")
      (footprint "eagle-import:R0603")
      (libsource (lib "eagle-import") (part "rcl_R-US_R0603"))
    )
    (comp (ref "R16")
      (value "100k")
      (footprint "eagle-import:R0603")
      (libsource (lib "eagle-import") (part "rcl_R-US_R0603"))
    )
    (comp (ref "TP3") (value "TP") (footprint "eagle-import:TP") (libsource (lib "eagle-import") (part "TP")))
    (comp (ref "TP4") (value "TP") (footprint "eagle-import:TP") (libsource (lib "eagle-import") (part "TP")))
    (comp (ref "TP5") (value "TP") (footprint "eagle-import:TP") (libsource (lib "eagle-import") (part "TP")))
    (comp (ref "TP6") (value "TP") (footprint "eagle-import:TP") (libsource (lib "eagle-import") (part "TP")))
    (comp (ref "TP7") (value "TP") (footprint "eagle-import:TP") (libsource (lib "eagle-import") (part "TP")))
    (comp (ref "TP8") (value "TP") (footprint "eagle-import:TP") (libsource (lib "eagle-import") (part "TP")))
    (comp (ref "X1")
      (value "SD-502702-003-1")
      (footprint "eagle-import:SD-502702-003")
      (libsource (lib "eagle-import") (part "SD-502702-003-1"))
    )
    (comp (ref "C31")
      (value ".1u")
      (footprint "eagle-import:C0603")
      (libsource (lib "eagle-import") (part "C-USC0603"))
    )
    (comp (ref "C32")
      (value "4.7u")
      (footprint "eagle-import:CSMD0805")
      (libsource (lib "eagle-import") (part "CSMD0805"))
    )
    (comp (ref "C33")
      (value "0.1u")
      (footprint "eagle-import:C0603")
      (libsource (lib "eagle-import") (part "C-EUC0603"))
    )
    (comp (ref "C34")
      (value "4u7")
      (footprint "eagle-import:C0603")
      (libsource (lib "eagle-import") (part "C-EUC0603"))
    )
    (comp (ref "C35")
      (value "10p")
      (footprint "eagle-import:C0603")
      (libsource (lib "eagle-import") (part "C-EUC0603"))
    )
    (comp (ref "C36")
      (value "10p")
      (footprint "eagle-import:C0603")
      (libsource (lib "eagle-import") (part "C-EUC0603"))
    )
    (comp (ref "D1")
      (value "SCHOTTKY")
      (footprint "eagle-import:MINIMELF")
      (libsource (lib "eagle-import") (part "SCHOTTKY-MINI-MELF"))
    )
    (comp (ref "J12")
      (value "eZ-RF1")
      (footprint "eagle-import:_MSP430_RF_MA09-2")
      (libsource (lib "eagle-import") (part "_MSP430_RF_MA09-2"))
    )
    (comp (ref "J13")
      (value "eZRF")
      (footprint "eagle-import:SL127L6")
      (libsource (lib "eagle-import") (part "SL127P6"))
    )
    (comp (ref "JP14")
      (value "RF_PWR")
      (footprint "eagle-import:JP1")
      (libsource (lib "eagle-import") (part "JP1E"))
    )
    (comp (ref "JP15")
      (value "USB_PWR")
      (footprint "eagle-import:JP1")
      (libsource (lib "eagle-import") (part "JP1E"))
    )
    (comp (ref "R22")
      (value "27R")
      (footprint "eagle-import:R0603")
      (libsource (lib "eagle-import") (part "rcl_R-US_R0603"))
    )
    (comp (ref "R23")
      (value "27R")
      (footprint "eagle-import:R0603")
      (libsource (lib "eagle-import") (part "rcl_R-US_R0603"))
    )
    (comp (ref "R24")
      (value "1M")
      (footprint "eagle-import:R0603")
      (libsource (lib "eagle-import") (part "rcl_R-US_R0603"))
    )
    (comp (ref "R25")
      (value "1k4")
      (footprint "eagle-import:R0603")
      (libsource (lib "eagle-import") (part "rcl_R-US_R0603"))
    )
    (comp (ref "R26")
      (value "100R")
      (footprint "eagle-import:R0603")
      (libsource (lib "eagle-import") (part "rcl_R-US_R0603"))
    )
    (comp (ref "R27")
      (value "33k")
      (footprint "eagle-import:R0603")
      (libsource (lib "eagle-import") (part "rcl_R-US_R0603"))
    )
    (comp (ref "RF1")
      (value "TFM-110-02-SM-D-A-K")
      (footprint "eagle-import:TFM-110-02-SM-D-A-K")
      (libsource (lib "eagle-import") (part "TFM-110-02-SM-D-A-K"))
    )
    (comp (ref "RF2")
      (value "TFM-110-02-SM-D-A-K")
      (footprint "eagle-import:TFM-110-02-SM-D-A-K")
      (libsource (lib "eagle-import") (part "TFM-110-02-SM-D-A-K"))
    )
    (comp (ref "S4")
      (value "USB_BSL")
      (footprint "eagle-import:PBTH")
      (libsource (lib "eagle-import") (part "PB"))
    )
    (comp (ref "U6")
      (value "TPD2E001DRLR")
      (footprint "eagle-import:TPD2E001-DRL")
      (libsource (lib "eagle-import") (part "TPD2E001"))
    )
    (comp (ref "USB1")
      (value "F5529 Mini-USB")
      (footprint "eagle-import:USB-MB-H")
      (libsource (lib "eagle-import") (part "USB-MB-H"))
    )
    (comp (ref "C20")
      (value "100n")
      (footprint "eagle-import:0402")
      (libsource (lib "eagle-import") (part "C_SMD0402"))
    )
    (comp (ref "C21")
      (value "10UF")
      (footprint "eagle-import:ELKO_B")
      (fields
        (field (name "MANUFACTURER") "Panasonic")
        (field (name "C_CATEGORY") "ALU")
        (field (name "MPN") "EEE1AA100NR")
        (field (name "V_RATING") "10V")
      )
      (libsource (lib "eagle-import") (part "FK-B4,7UF/35V"))
    )
    (comp (ref "R58")
      (value "0R")
      (footprint "eagle-import:R0603")
      (libsource (lib "eagle-import") (part "rcl_R-US_R0603"))
    )
    (comp (ref "U2")
      (value "LIS3DH")
      (footprint "eagle-import:LGA16R50P3X5_300X300X100")
      (fields (field (name "MANUFACTURER") "ST Microelectronics"))
      (libsource (lib "eagle-import") (part "LIS3DH"))
    )
    (comp (ref "C22")
      (value "1µF")
      (footprint "eagle-import:CSMD0805")
      (libsource (lib "eagle-import") (part "CSMD0805"))
    )
    (comp (ref "C23")
      (value "1µF")
      (footprint "eagle-import:CSMD0805")
      (libsource (lib "eagle-import") (part "CSMD0805"))
    )
    (comp (ref "C24")
      (value "1µF")
      (footprint "eagle-import:CSMD0805")
      (libsource (lib "eagle-import") (part "CSMD0805"))
    )
    (comp (ref "C25")
      (value "1µF")
      (footprint "eagle-import:CSMD0805")
      (libsource (lib "eagle-import") (part "CSMD0805"))
    )
    (comp (ref "C26")
      (value "1µF")
      (footprint "eagle-import:CSMD0805")
      (libsource (lib "eagle-import") (part "CSMD0805"))
    )
    (comp (ref "C27")
      (value "1µF")
      (footprint "eagle-import:CSMD0805")
      (libsource (lib "eagle-import") (part "CSMD0805"))
    )
    (comp (ref "C28")
      (value "4.7uF")
      (footprint "eagle-import:CSMD0805")
      (libsource (lib "eagle-import") (part "CSMD0805"))
    )
    (comp (ref "C29")
      (value "10nF")
      (footprint "eagle-import:CSMD0805")
      (libsource (lib "eagle-import") (part "CSMD0805"))
    )
    (comp (ref "C30")
      (value "1µF")
      (footprint "eagle-import:CSMD0805")
      (libsource (lib "eagle-import") (part "CSMD0805"))
    )
    (comp (ref "J9")
      (value "MOLEX3PIN")
      (footprint "eagle-import:MOLEX-3P-HEADER")
      (libsource (lib "eagle-import") (part "MOLEX3PIN"))
    )
    (comp (ref "J10")
      (value "PWR")
      (footprint "eagle-import:1X03")
      (libsource (lib "eagle-import") (part "PINHD-1X3"))
    )
    (comp (ref "JP6")
      (value "430_PWR")
      (footprint "eagle-import:JP1")
      (libsource (lib "eagle-import") (part "JP1E"))
    )
    (comp (ref "JP7")
      (value "SYS_PWR")
      (footprint "eagle-import:JP1")
      (libsource (lib "eagle-import") (part "JP1E"))
    )
    (comp (ref "JP8")
      (value "LDO_PWR_SEL")
      (footprint "eagle-import:1X03S")
      (libsource (lib "eagle-import") (part "PINHD-1X3/SMALL_PIN"))
    )
    (comp (ref "JP11")
      (value "JTAG_PWR_SEN")
      (footprint "eagle-import:1X03S")
      (libsource (lib "eagle-import") (part "PINHD-1X3/SMALL_PIN"))
    )
    (comp (ref "R17")
      (value "47k")
      (footprint "eagle-import:R0603")
      (libsource (lib "eagle-import") (part "rcl_R-US_R0603"))
    )
    (comp (ref "R18")
      (value "47k")
      (footprint "eagle-import:R0603")
      (libsource (lib "eagle-import") (part "rcl_R-US_R0603"))
    )
    (comp (ref "R19")
      (value "0")
      (footprint "eagle-import:R0603")
      (libsource (lib "eagle-import") (part "rcl_R-US_R0603"))
    )
    (comp (ref "R20")
      (value "100k")
      (footprint "eagle-import:R0603")
      (libsource (lib "eagle-import") (part "rcl_R-US_R0603"))
    )
    (comp (ref "R21")
      (value "36k 1%")
      (footprint "eagle-import:R0603")
      (libsource (lib "eagle-import") (part "rcl_R-US_R0603"))
    )
    (comp (ref "SW1")
      (value "3PDT")
      (footprint "eagle-import:3PDT")
      (libsource (lib "eagle-import") (part "3PDT"))
    )
    (comp (ref "U3")
      (value "EA DOGS102-6 (LCD Display)")
      (footprint "eagle-import:EADOGS102-6")
      (libsource (lib "eagle-import") (part "EADOGS102-6"))
    )
    (comp (ref "U4")
      (value "TPS73533")
      (footprint "eagle-import:DRB_S-PVSON-N8")
      (libsource (lib "eagle-import") (part "TPS735"))
    )
    (comp (ref "U5")
      (value "TPS75105DSKR")
      (footprint "eagle-import:DSK_S-PDSO-N10")
      (libsource (lib "eagle-import") (part "TPS7510X"))
    )
    (comp (ref "C37")
      (value "10n")
      (footprint "eagle-import:0402")
      (libsource (lib "eagle-import") (part "C_SMD0402"))
    )
    (comp (ref "C38")
      (value "33p")
      (footprint "eagle-import:0402")
      (libsource (lib "eagle-import") (part "C_SMD0402"))
    )
    (comp (ref "C39")
      (value "33p")
      (footprint "eagle-import:0402")
      (libsource (lib "eagle-import") (part "C_SMD0402"))
    )
    (comp (ref "C40")
      (value "1u/6.3V")
      (footprint "eagle-import:0603")
      (libsource (lib "eagle-import") (part "C_SMD0603"))
    )
    (comp (ref "C41")
      (value "100n")
      (footprint "eagle-import:0402")
      (libsource (lib "eagle-import") (part "C_SMD0402"))
    )
    (comp (ref "J17")
      (value "SL127L6TH")
      (footprint "eagle-import:SL127L6_MPE")
      (libsource (lib "eagle-import") (part "SL127L6TH"))
    )
    (comp (ref "JP16")
      (value "eZ430-FET_JMP")
      (footprint "eagle-import:JP5Q")
      (libsource (lib "eagle-import") (part "JP5Q"))
    )
    (comp (ref "LED9")
      (value "green")
      (footprint "eagle-import:DIODE0603")
      (libsource (lib "eagle-import") (part "LED_0603D0603"))
    )
    (comp (ref "Q3")
      (value "12MHz")
      (footprint "eagle-import:FT10A")
      (libsource (lib "eagle-import") (part "XTL_FT7AFT10A"))
    )
    (comp (ref "R28")
      (value "47k")
      (footprint "eagle-import:0402")
      (libsource (lib "eagle-import") (part "R_SMDR0402"))
    )
    (comp (ref "R29")
      (value "47k")
      (footprint "eagle-import:0402")
      (libsource (lib "eagle-import") (part "R_SMDR0402"))
    )
    (comp (ref "R30")
      (value "47k")
      (footprint "eagle-import:0402")
      (libsource (lib "eagle-import") (part "R_SMDR0402"))
    )
    (comp (ref "R31")
      (value "100R")
      (footprint "eagle-import:0402")
      (libsource (lib "eagle-import") (part "R_SMDR0402"))
    )
    (comp (ref "R32")
      (value "100R")
      (footprint "eagle-import:0402")
      (libsource (lib "eagle-import") (part "R_SMDR0402"))
    )
    (comp (ref "R33")
      (value "270")
      (footprint "eagle-import:0402")
      (libsource (lib "eagle-import") (part "R_SMDR0402"))
    )
    (comp (ref "R34")
      (value "DNP")
      (footprint "eagle-import:0402")
      (libsource (lib "eagle-import") (part "R_SMDR0402"))
    )
    (comp (ref "R35")
      (value "100R")
      (footprint "eagle-import:0402")
      (libsource (lib "eagle-import") (part "R_SMDR0402"))
    )
    (comp (ref "R36")
      (value "100R")
      (footprint "eagle-import:0402")
      (libsource (lib "eagle-import") (part "R_SMDR0402"))
    )
    (comp (ref "TP9")
      (value "TP05TP10")
      (footprint "eagle-import:TP10")
      (libsource (lib "eagle-import") (part "TP05TP10"))
    )
    (comp (ref "TP10")
      (value "TP05TP10")
      (footprint "eagle-import:TP10")
      (libsource (lib "eagle-import") (part "TP05TP10"))
    )
    (comp (ref "TP11")
      (value "TP05TP10")
      (footprint "eagle-import:TP10")
      (libsource (lib "eagle-import") (part "TP05TP10"))
    )
    (comp (ref "TP12")
      (value "TP05TP10")
      (footprint "eagle-import:TP10")
      (libsource (lib "eagle-import") (part "TP05TP10"))
    )
    (comp (ref "TP13")
      (value "TP05TP10")
      (footprint "eagle-import:TP10")
      (libsource (lib "eagle-import") (part "TP05TP10"))
    )
    (comp (ref "TP14")
      (value "TP05TP10")
      (footprint "eagle-import:TP10")
      (libsource (lib "eagle-import") (part "TP05TP10"))
    )
    (comp (ref "TP15")
      (value "TP05TP10")
      (footprint "eagle-import:TP10")
      (libsource (lib "eagle-import") (part "TP05TP10"))
    )
    (comp (ref "U7")
      (value "MSP430F1612IPMR")
      (footprint "eagle-import:PM_PAG64")
      (libsource (lib "eagle-import") (part "F16X---PM64"))
    )
    (comp (ref "U8")
      (value "TXS0104EPWR")
      (footprint "eagle-import:PW_R-PDSO-G14")
      (libsource (lib "eagle-import") (part "TXS0104E"))
    )
  )
  (nets
    (net (code "5") (name "5529_LDO") (class "Default")
      (node (ref "C5") (pin "1") (pinfunction "1_1") (pintype "passive"))
      (node (ref "C7") (pin "1") (pinfunction "1_1") (pintype "passive"))
      (node (ref "C9") (pin "1") (pinfunction "1_1") (pintype "passive"))
      (node (ref "JP8") (pin "1") (pinfunction "1_1") (pintype "passive"))
      (node (ref "S4") (pin "1") (pinfunction "P_1") (pintype "passive"))
      (node (ref "U1") (pin "66") (pinfunction "66_66") (pintype "power_in"))
    )
    (net (code "6") (name "5529_VBUS") (class "Default")
      (node (ref "C27") (pin "2") (pinfunction "2_2") (pintype "passive"))
      (node (ref "C33") (pin "1") (pinfunction "1_1") (pintype "passive"))
      (node (ref "C34") (pin "1") (pinfunction "1_1") (pintype "passive"))
      (node (ref "JP15") (pin "1") (pinfunction "1_1") (pintype "passive"))
      (node (ref "R19") (pin "2") (pinfunction "2_2") (pintype "passive"))
      (node (ref "U1") (pin "65") (pinfunction "65_65") (pintype "power_in"))
      (node (ref "U4") (pin "8") (pinfunction "IN_8") (pintype "power_in"))
    )
    (net (code "7") (name "A5") (class "Default")
      (node (ref "POT1") (pin "2") (pinfunction "TAP_2") (pintype "passive"))
      (node (ref "U1") (pin "2") (pinfunction "2_2") (pintype "bidirectional"))
    )
    (net (code "8") (name "ACCEL_CS") (class "Default")
      (node (ref "U1") (pin "42") (pinfunction "42_42") (pintype "bidirectional"))
      (node (ref "U2") (pin "8") (pinfunction "CS_8") (pintype "input"))
    )
    (net (code "9") (name "ACCEL_INT1") (class "Default")
      (node (ref "U1") (pin "34") (pinfunction "34_34") (pintype "bidirectional"))
      (node (ref "U2") (pin "11") (pinfunction "INT1_11") (pintype "output"))
    )
    (net (code "10") (name "ACCEL_PWR") (class "Default")
      (node (ref "C20") (pin "2") (pinfunction "2_2") (pintype "passive"))
      (node (ref "C21") (pin "+") (pinfunction "+_+") (pintype "passive"))
      (node (ref "U1") (pin "43") (pinfunction "43_43") (pintype "bidirectional"))
      (node (ref "U2") (pin "1") (pinfunction "VDD_IO_1") (pintype "power_in"))
      (node (ref "U2") (pin "14") (pinfunction "VDD_14") (pintype "power_in"))
    )
    (net (code "11") (name "ACCEL_SCK") (class "Default")
      (node (ref "U1") (pin "36") (pinfunction "36_36") (pintype "bidirectional"))
      (node (ref "U2") (pin "4") (pinfunction "SCL/SPC_4") (pintype "input"))
    )
    (net (code "12") (name "ACCEL_SIMO") (class "Default")
      (node (ref "U1") (pin "40") (pinfunction "40_40") (pintype "bidirectional"))
      (node (ref "U2") (pin "6") (pinfunction "SDA/SDI/SDO_6") (pintype "bidirectional"))
    )
    (net (code "13") (name "ACCEL_SOMI") (class "Default")
      (node (ref "U1") (pin "41") (pinfunction "41_41") (pintype "bidirectional"))
      (node (ref "U2") (pin "7") (pinfunction "SDO/SA0_7") (pintype "output"))
    )
    (net (code "14") (name "ALT_LDO") (class "Default")
      (node (ref "C28") (pin "2") (pinfunction "2_2") (pintype "passive"))
      (node (ref "JP8") (pin "3") (pinfunction "3_3") (pintype "passive"))
      (node (ref "SW1") (pin "1") (pinfunction "A1_1") (pintype "bidirectional"))
      (node (ref "U4") (pin "1") (pinfunction "OUT_1") (pintype "output"))
    )
    (net (code "15") (name "AVCC") (class "Default")
      (node (ref "C13") (pin "1") (pinfunction "1_1") (pintype "passive"))
      (node (ref "C50") (pin "+") (pinfunction "+_+") (pintype "passive"))
      (node (ref "R2") (pin "1") (pinfunction "1_1") (pintype "passive"))
      (node (ref "U1") (pin "11") (pinfunction "11_11") (pintype "power_in"))
    )
    (net (code "16") (name "BRXD") (class "Default")
      (node (ref "J17") (pin "6") (pinfunction "6_6") (pintype "passive"))
      (node (ref "R35") (pin "2") (pinfunction "2_2") (pintype "passive"))
      (node (ref "U8") (pin "10") (pinfunction "B4_10") (pintype "output"))
    )
    (net (code "17") (name "BRXDI") (class "Default")
      (node (ref "R35") (pin "1") (pinfunction "1_1") (pintype "passive"))
      (node (ref "R45") (pin "1") (pinfunction "1_1") (pintype "passive"))
      (node (ref "U10") (pin "32") (pinfunction "P3.0_32") (pintype "bidirectional"))
      (node (ref "U7") (pin "35") (pinfunction "35_35") (pintype "bidirectional"))
    )
    (net (code "18") (name "BTXD") (class "Default")
      (node (ref "J17") (pin "1") (pinfunction "1_1") (pintype "passive"))
      (node (ref "R36") (pin "2") (pinfunction "2_2") (pintype "passive"))
      (node (ref "U8") (pin "11") (pinfunction "B3_11") (pintype "output"))
    )
    (net (code "19") (name "BTXDI") (class "Default")
      (node (ref "R36") (pin "1") (pinfunction "1_1") (pintype "passive"))
      (node (ref "R44") (pin "1") (pinfunction "1_1") (pintype "passive"))
      (node (ref "U10") (pin "31") (pinfunction "P3.1_31") (pintype "bidirectional"))
      (node (ref "U7") (pin "34") (pinfunction "34_34") (pintype "bidirectional"))
    )
    (net (code "20") (name "CB0") (class "Default")
      (node (ref "PAD1") (pin "1") (pinfunction "IN_1") (pintype "bidirectional"))
      (node (ref "R14") (pin "2") (pinfunction "2_2") (pintype "passive"))
      (node (ref "U1") (pin "77") (pinfunction "77_77") (pintype "bidirectional"))
    )
    (net (code "21") (name "CB1") (class "Default")
      (node (ref "PAD2") (pin "1") (pinfunction "IN_1") (pintype "bidirectional"))
      (node (ref "R15") (pin "2") (pinfunction "2_2") (pintype "passive"))
      (node (ref "U1") (pin "78") (pinfunction "78_78") (pintype "bidirectional"))
    )
    (net (code "22") (name "CB2") (class "Default")
      (node (ref "PAD3") (pin "1") (pinfunction "IN_1") (pintype "bidirectional"))
      (node (ref "R16") (pin "1") (pinfunction "1_1") (pintype "passive"))
      (node (ref "U1") (pin "79") (pinfunction "79_79") (pintype "bidirectional"))
    )
    (net (code "23") (name "CB3") (class "Default")
      (node (ref "PAD4") (pin "1") (pinfunction "IN_1") (pintype "bidirectional"))
      (node (ref "R12") (pin "2") (pinfunction "2_2") (pintype "passive"))
      (node (ref "U1") (pin "80") (pinfunction "80_80") (pintype "bidirectional"))
    )
    (net (code "24") (name "CB4") (class "Default")
      (node (ref "PAD5") (pin "1") (pinfunction "IN_1") (pintype "bidirectional"))
      (node (ref "R13") (pin "2") (pinfunction "2_2") (pintype "passive"))
      (node (ref "U1") (pin "1") (pinfunction "1_1") (pintype "bidirectional"))
    )
    (net (code "25") (name "CBOUT") (class "Default")
      (node (ref "R12") (pin "1") (pinfunction "1_1") (pintype "passive"))
      (node (ref "R13") (pin "1") (pinfunction "1_1") (pintype "passive"))
      (node (ref "R14") (pin "1") (pinfunction "1_1") (pintype "passive"))
      (node (ref "R15") (pin "1") (pinfunction "1_1") (pintype "passive"))
      (node (ref "R16") (pin "2") (pinfunction "2_2") (pintype "passive"))
      (node (ref "U1") (pin "27") (pinfunction "27_27") (pintype "bidirectional"))
    )
    (net (code "26") (name "CLK3410") (class "Default")
      (node (ref "R49") (pin "2") (pinfunction "2_2") (pintype "passive"))
      (node (ref "U7") (pin "49") (pinfunction "49_49") (pintype "bidirectional"))
    )
    (net (code "27") (name "DVCC") (class "Default")
      (node (ref "C10") (pin "+") (pinfunction "+_+") (pintype "passive"))
      (node (ref "C11") (pin "2") (pinfunction "2_2") (pintype "passive"))
      (node (ref "C12") (pin "1") (pinfunction "1_1") (pintype "passive"))
      (node (ref "C15") (pin "+") (pinfunction "+_+") (pintype "passive"))
      (node (ref "C16") (pin "2") (pinfunction "2_2") (pintype "passive"))
      (node (ref "JP11") (pin "2") (pinfunction "2_2") (pintype "passive"))
      (node (ref "JP16") (pin "9") (pinfunction "9_9") (pintype "passive"))
      (node (ref "JP6") (pin "2") (pinfunction "2_2") (pintype "passive"))
      (node (ref "R1") (pin "2") (pinfunction "2_2") (pintype "passive"))
      (node (ref "R2") (pin "2") (pinfunction "2_2") (pintype "passive"))
      (node (ref "U1") (pin "18") (pinfunction "18_18") (pintype "power_in"))
      (node (ref "U1") (pin "50") (pinfunction "50_50") (pintype "power_in"))
    )
    (net (code "28") (name "EZ_D+") (class "Default")
      (node (ref "R43") (pin "1") (pinfunction "1_1") (pintype "passive"))
      (node (ref "U11") (pin "5") (pinfunction "IO2_5") (pintype "bidirectional"))
      (node (ref "USB2") (pin "D+") (pinfunction "D+_D+") (pintype "bidirectional"))
    )
    (net (code "29") (name "EZ_D-") (class "Default")
      (node (ref "R46") (pin "1") (pinfunction "1_1") (pintype "passive"))
      (node (ref "U11") (pin "3") (pinfunction "IO1_3") (pintype "bidirectional"))
      (node (ref "USB2") (pin "D-") (pinfunction "D-_D-") (pintype "bidirectional"))
    )
    (net (code "30") (name "EZ_VBUS") (class "Default")
      (node (ref "C43") (pin "2") (pinfunction "2_2") (pintype "passive"))
      (node (ref "TP9") (pin "1") (pinfunction "1_1") (pintype "passive"))
      (node (ref "U11") (pin "1") (pinfunction "VCC_1") (pintype "power_in"))
      (node (ref "U9") (pin "5") (pinfunction "IN1_5") (pintype "input"))
      (node (ref "U9") (pin "6") (pinfunction "IN2_6") (pintype "input"))
      (node (ref "USB2") (pin "VBUS") (pinfunction "VBUS_VBUS") (pintype "bidirectional"))
    )
    (net (code "31") (name "EZ_VCC") (class "Default")
      (node (ref "C40") (pin "2") (pinfunction "2_2") (pintype "passive"))
      (node (ref "C41") (pin "1") (pinfunction "1_1") (pintype "passive"))
      (node (ref "C42") (pin "1") (pinfunction "1_1") (pintype "passive"))
      (node (ref "C47") (pin "2") (pinfunction "2_2") (pintype "passive"))
      (node (ref "C48") (pin "2") (pinfunction "2_2") (pintype "passive"))
      (node (ref "C49") (pin "1") (pinfunction "1_1") (pintype "passive"))
      (node (ref "J17") (pin "2") (pinfunction "2_2") (pintype "passive"))
      (node (ref "R28") (pin "2") (pinfunction "2_2") (pintype "passive"))
      (node (ref "R30") (pin "2") (pinfunction "2_2") (pintype "passive"))
      (node (ref "R33") (pin "2") (pinfunction "2_2") (pintype "passive"))
      (node (ref "R37") (pin "2") (pinfunction "2_2") (pintype "passive"))
      (node (ref "R39") (pin "2") (pinfunction "2_2") (pintype "passive"))
      (node (ref "R40") (pin "2") (pinfunction "2_2") (pintype "passive"))
      (node (ref "R44") (pin "2") (pinfunction "2_2") (pintype "passive"))
      (node (ref "R45") (pin "2") (pinfunction "2_2") (pintype "passive"))
      (node (ref "R47") (pin "2") (pinfunction "2_2") (pintype "passive"))
      (node (ref "R53") (pin "1") (pinfunction "1_1") (pintype "passive"))
      (node (ref "R54") (pin "1") (pinfunction "1_1") (pintype "passive"))
      (node (ref "SW1") (pin "2") (pinfunction "B1_2") (pintype "bidirectional"))
      (node (ref "SW1") (pin "6") (pinfunction "B2_6") (pintype "bidirectional"))
      (node (ref "U10") (pin "23") (pinfunction "TEST0_23") (pintype "input"))
      (node (ref "U10") (pin "24") (pinfunction "TEST1_24") (pintype "input"))
      (node (ref "U10") (pin "25") (pinfunction "VCC1_25") (pintype "power_in"))
      (node (ref "U10") (pin "3") (pinfunction "VCC_3") (pintype "power_in"))
      (node (ref "U12") (pin "8") (pinfunction "VCC_8") (pintype "input"))
      (node (ref "U7") (pin "1") (pinfunction "1_1") (pintype "power_in"))
      (node (ref "U7") (pin "64") (pinfunction "64_64") (pintype "power_in"))
      (node (ref "U8") (pin "14") (pinfunction "VCCB_14") (pintype "power_in"))
      (node (ref "U9") (pin "7") (pinfunction "OUT2_7") (pintype "power_in"))
      (node (ref "U9") (pin "8") (pinfunction "OUT1_8") (pintype "power_in"))
    )
    (net (code "32") (name "GND") (class "Default")
      (node (ref "C10") (pin "-") (pinfunction "-_-") (pintype "passive"))
      (node (ref "C11") (pin "1") (pinfunction "1_1") (pintype "passive"))
      (node (ref "C12") (pin "2") (pinfunction "2_2") (pintype "passive"))
      (node (ref "C13") (pin "2") (pinfunction "2_2") (pintype "passive"))
      (node (ref "C14") (pin "1") (pinfunction "1_1") (pintype "passive"))
      (node (ref "C15") (pin "-") (pinfunction "-_-") (pintype "passive"))
      (node (ref "C16") (pin "1") (pinfunction "1_1") (pintype "passive"))
      (node (ref "C17") (pin "1") (pinfunction "1_1") (pintype "passive"))
      (node (ref "C18") (pin "1") (pinfunction "1_1") (pintype "passive"))
      (node (ref "C19") (pin "1") (pinfunction "1_1") (pintype "passive"))
      (node (ref "C20") (pin "1") (pinfunction "1_1") (pintype "passive"))
      (node (ref "C21") (pin "-") (pinfunction "-_-") (pintype "passive"))
      (node (ref "C22") (pin "2") (pinfunction "2_2") (pintype "passive"))
      (node (ref "C23") (pin "1") (pinfunction "1_1") (pintype "passive"))
      (node (ref "C24") (pin "1") (pinfunction "1_1") (pintype "passive"))
      (node (ref "C27") (pin "1") (pinfunction "1_1") (pintype "passive"))
      (node (ref "C28") (pin "1") (pinfunction "1_1") (pintype "passive"))
      (node (ref "C29") (pin "1") (pinfunction "1_1") (pintype "passive"))
      (node (ref "C3") (pin "1") (pinfunction "1_1") (pintype "passive"))
      (node (ref "C30") (pin "1") (pinfunction "1_1") (pintype "passive"))
      (node (ref "C31") (pin "2") (pinfunction "2_2") (pintype "passive"))
      (node (ref "C32") (pin "2") (pinfunction "2_2") (pintype "passive"))
      (node (ref "C33") (pin "2") (pinfunction "2_2") (pintype "passive"))
      (node (ref "C34") (pin "2") (pinfunction "2_2") (pintype "passive"))
      (node (ref "C35") (pin "2") (pinfunction "2_2") (pintype "passive"))
      (node (ref "C36") (pin "2") (pinfunction "2_2") (pintype "passive"))
      (node (ref "C37") (pin "2") (pinfunction "2_2") (pintype "passive"))
      (node (ref "C38") (pin "2") (pinfunction "2_2") (pintype "passive"))
      (node (ref "C39") (pin "2") (pinfunction "2_2") (pintype "passive"))
      (node (ref "C40") (pin "1") (pinfunction "1_1") (pintype "passive"))
      (node (ref "C41") (pin "2") (pinfunction "2_2") (pintype "passive"))
      (node (ref "C42") (pin "2") (pinfunction "2_2") (pintype "passive"))
      (node (ref "C43") (pin "1") (pinfunction "1_1") (pintype "passive"))
      (node (ref "C44") (pin "2") (pinfunction "2_2") (pintype "passive"))
      (node (ref "C45") (pin "1") (pinfunction "1_1") (pintype "passive"))
      (node (ref "C46") (pin "1") (pinfunction "1_1") (pintype "passive"))
      (node (ref "C47") (pin "1") (pinfunction "1_1") (pintype "passive"))
      (node (ref "C48") (pin "1") (pinfunction "1_1") (pintype "passive"))
      (node (ref "C49") (pin "2") (pinfunction "2_2") (pintype "passive"))
      (node (ref "C5") (pin "2") (pinfunction "2_2") (pintype "passive"))
      (node (ref "C50") (pin "-") (pinfunction "-_-") (pintype "passive"))
      (node (ref "C7") (pin "2") (pinfunction "2_2") (pintype "passive"))
      (node (ref "C8") (pin "2") (pinfunction "2_2") (pintype "passive"))
      (node (ref "C9") (pin "2") (pinfunction "2_2") (pintype "passive"))
      (node (ref "CON2") (pin "7") (pinfunction "7_7") (pintype "bidirectional"))
      (node (ref "CON2") (pin "8") (pinfunction "8_8") (pintype "bidirectional"))
      (node (ref "J1") (pin "9") (pinfunction "9_9") (pintype "passive"))
      (node (ref "J10") (pin "1") (pinfunction "1_1") (pintype "passive"))
      (node (ref "J10") (pin "2") (pinfunction "2_2") (pintype "passive"))
      (node (ref "J12") (pin "1") (pinfunction "1_1") (pintype "passive"))
      (node (ref "J12") (pin "12") (pinfunction "12_12") (pintype "passive"))
      (node (ref "J13") (pin "5") (pinfunction "5_5") (pintype "bidirectional"))
      (node (ref "J17") (pin "5") (pinfunction "5_5") (pintype "passive"))
      (node (ref "J4") (pin "13") (pinfunction "13_13") (pintype "passive"))
      (node (ref "J5") (pin "13") (pinfunction "13_13") (pintype "passive"))
      (node (ref "J9") (pin "2") (pinfunction "2_2") (pintype "bidirectional"))
      (node (ref "J9") (pin "3") (pinfunction "3_3") (pintype "bidirectional"))
      (node (ref "LED1") (pin "C") (pinfunction "C_C") (pintype "passive"))
      (node (ref "LED2") (pin "C") (pinfunction "C_C") (pintype "passive"))
      (node (ref "LED3") (pin "C") (pinfunction "C_C") (pintype "passive"))
      (node (ref "LED4") (pin "C") (pinfunction "C_C") (pintype "passive"))
      (node (ref "LED5") (pin "C") (pinfunction "C_C") (pintype "passive"))
      (node (ref "LED6") (pin "C") (pinfunction "C_C") (pintype "passive"))
      (node (ref "LED7") (pin "C") (pinfunction "C_C") (pintype "passive"))
      (node (ref "LED8") (pin "C") (pinfunction "C_C") (pintype "passive"))
      (node (ref "LED9") (pin "K") (pinfunction "C_K") (pintype "passive"))
      (node (ref "POT1") (pin "3") (pinfunction "CW_3") (pintype "passive"))
      (node (ref "R20") (pin "1") (pinfunction "1_1") (pintype "passive"))
      (node (ref "R21") (pin "1") (pinfunction "1_1") (pintype "passive"))
      (node (ref "R24") (pin "1") (pinfunction "1_1") (pintype "passive"))
      (node (ref "R27") (pin "1") (pinfunction "1_1") (pintype "passive"))
      (node (ref "R29") (pin "2") (pinfunction "2_2") (pintype "passive"))
      (node (ref "R34") (pin "1") (pinfunction "1_1") (pintype "passive"))
      (node (ref "R38") (pin "1") (pinfunction "1_1") (pintype "passive"))
      (node (ref "R48") (pin "1") (pinfunction "1_1") (pintype "passive"))
      (node (ref "R50") (pin "1") (pinfunction "1_1") (pintype "passive"))
      (node (ref "R51") (pin "2") (pinfunction "2_2") (pintype "passive"))
      (node (ref "RF1") (pin "1") (pinfunction "1_1") (pintype "passive"))
      (node (ref "RF1") (pin "19") (pinfunction "19_19") (pintype "passive"))
      (node (ref "RF2") (pin "2") (pinfunction "2_2") (pintype "passive"))
      (node (ref "S1") (pin "2") (pinfunction "S_2") (pintype "passive"))
      (node (ref "S2") (pin "2") (pinfunction "S_2") (pintype "passive"))
      (node (ref "S3") (pin "2") (pinfunction "S_2") (pintype "passive"))
      (node (ref "TP11") (pin "1") (pinfunction "1_1") (pintype "passive"))
      (node (ref "U1") (pin "14") (pinfunction "14_14") (pintype "power_in"))
      (node (ref "U1") (pin "19") (pinfunction "19_19") (pintype "power_in"))
      (node (ref "U1") (pin "49") (pinfunction "49_49") (pintype "power_in"))
      (node (ref "U1") (pin "61") (pinfunction "61_61") (pintype "power_in"))
      (node (ref "U1") (pin "68") (pinfunction "68_68") (pintype "power_in"))
      (node (ref "U10") (pin "15") (pinfunction "DCD_15") (pintype "input"))
      (node (ref "U10") (pin "16") (pinfunction "RI/CP_16") (pintype "input"))
      (node (ref "U10") (pin "18") (pinfunction "GND1_18") (pintype "power_in"))
      (node (ref "U10") (pin "28") (pinfunction "GND2_28") (pintype "power_in"))
      (node (ref "U10") (pin "8") (pinfunction "GND_8") (pintype "power_in"))
      (node (ref "U11") (pin "4") (pinfunction "GND_4") (pintype "power_in"))
      (node (ref "U12") (pin "1") (pinfunction "E0_1") (pintype "input"))
      (node (ref "U12") (pin "2") (pinfunction "E1_2") (pintype "input"))
      (node (ref "U12") (pin "3") (pinfunction "E2_3") (pintype "power_in"))
      (node (ref "U12") (pin "4") (pinfunction "VSS_4") (pintype "input"))
      (node (ref "U12") (pin "7") (pinfunction "WC_7") (pintype "passive"))
      (node (ref "U2") (pin "10") (pinfunction "RESERVED(TO_GND)_10") (pintype "passive"))
      (node (ref "U2") (pin "12") (pinfunction "GND_2_12") (pintype "power_in"))
      (node (ref "U2") (pin "5") (pinfunction "GND_1_5") (pintype "power_in"))
      (node (ref "U3") (pin "13") (pinfunction "C2-|CG_13") (pintype "power_in"))
      (node (ref "U3") (pin "2") (pinfunction "C1-|CR_2") (pintype "power_in"))
      (node (ref "U3") (pin "20") (pinfunction "VSS1_20") (pintype "power_in"))
      (node (ref "U3") (pin "21") (pinfunction "VSS2_21") (pintype "power_in"))
      (node (ref "U4") (pin "4") (pinfunction "GND_4") (pintype "power_in"))
      (node (ref "U5") (pin "5") (pinfunction "GND_5") (pintype "power_in"))
      (node (ref "U6") (pin "4") (pinfunction "GND_4") (pintype "power_in"))
      (node (ref "U7") (pin "62") (pinfunction "62_62") (pintype "power_in"))
      (node (ref "U7") (pin "63") (pinfunction "63_63") (pintype "power_in"))
      (node (ref "U8") (pin "7") (pinfunction "GND_7") (pintype "power_in"))
      (node (ref "U9") (pin "3") (pinfunction "GND_3") (pintype "power_in"))
      (node (ref "U9") (pin "4") (pinfunction "EN_4") (pintype "input"))
      (node (ref "USB1") (pin "GND") (pinfunction "GND_GND") (pintype "bidirectional"))
      (node (ref "USB2") (pin "GND") (pinfunction "GND_GND") (pintype "bidirectional"))
      (node (ref "X1") (pin "6") (pinfunction "VSS_6") (pintype "bidirectional"))
      (node (ref "X1") (pin "A") (pinfunction "A_A") (pintype "bidirectional"))
    )
    (net (code "33") (name "HTCK") (class "Default")
      (node (ref "TP12") (pin "1") (pinfunction "1_1") (pintype "passive"))
      (node (ref "U7") (pin "57") (pinfunction "57_57") (pintype "input"))
    )
    (net (code "34") (name "HTDI") (class "Default")
      (node (ref "TP14") (pin "1") (pinfunction "1_1") (pintype "passive"))
      (node (ref "U7") (pin "55") (pinfunction "55_55") (pintype "input"))
    )
    (net (code "35") (name "HTDO") (class "Default")
      (node (ref "TP15") (pin "1") (pinfunction "1_1") (pintype "passive"))
      (node (ref "U7") (pin "54") (pinfunction "54_54") (pintype "bidirectional"))
    )
    (net (code "36") (name "HTMS") (class "Default")
      (node (ref "TP13") (pin "1") (pinfunction "1_1") (pintype "passive"))
      (node (ref "U7") (pin "56") (pinfunction "56_56") (pintype "input"))
    )
    (net (code "37") (name "JTAG_PWR") (class "Default")
      (node (ref "J1") (pin "2") (pinfunction "2_2") (pintype "passive"))
      (node (ref "SW1") (pin "4") (pinfunction "C1_4") (pintype "bidirectional"))
      (node (ref "SW1") (pin "8") (pinfunction "C2_8") (pintype "bidirectional"))
    )
    (net (code "38") (name "JTAG_SENSE") (class "Default")
      (node (ref "J1") (pin "4") (pinfunction "4_4") (pintype "passive"))
      (node (ref "JP11") (pin "1") (pinfunction "1_1") (pintype "passive"))
    )
    (net (code "39") (name "LCD_BL_EN") (class "Default")
      (node (ref "R20") (pin "2") (pinfunction "2_2") (pintype "passive"))
      (node (ref "U1") (pin "59") (pinfunction "59_59") (pintype "bidirectional"))
      (node (ref "U5") (pin "1") (pinfunction "ENB_1") (pintype "input"))
      (node (ref "U5") (pin "2") (pinfunction "ENA_2") (pintype "input"))
    )
    (net (code "40") (name "LCD_CS") (class "Default")
      (node (ref "R18") (pin "2") (pinfunction "2_2") (pintype "passive"))
      (node (ref "U1") (pin "57") (pinfunction "57_57") (pintype "bidirectional"))
      (node (ref "U3") (pin "28") (pinfunction "~{CS0}_28") (pintype "input"))
    )
    (net (code "41") (name "LCD_D{slash}C") (class "Default")
      (node (ref "U1") (pin "55") (pinfunction "55_55") (pintype "bidirectional"))
      (node (ref "U3") (pin "26") (pinfunction "CD_26") (pintype "input"))
    )
    (net (code "42") (name "LCD_RST") (class "Default")
      (node (ref "R17") (pin "2") (pinfunction "2_2") (pintype "passive"))
      (node (ref "U1") (pin "56") (pinfunction "56_56") (pintype "bidirectional"))
      (node (ref "U3") (pin "27") (pinfunction "~{RST}_27") (pintype "input"))
    )
    (net (code "43") (name "LDO_SEL") (class "Default")
      (node (ref "JP8") (pin "2") (pinfunction "2_2") (pintype "passive"))
      (node (ref "SW1") (pin "5") (pinfunction "A2_5") (pintype "bidirectional"))
    )
    (net (code "44") (name "LFXTGND") (class "Default")
      (node (ref "C2") (pin "2") (pinfunction "2_2") (pintype "passive"))
      (node (ref "C4") (pin "2") (pinfunction "2_2") (pintype "passive"))
      (node (ref "Q1") (pin "P3") (pinfunction "GND_P3") (pintype "bidirectional"))
    )
    (net (code "45") (name "MSP_D+") (class "Default")
      (node (ref "R23") (pin "2") (pinfunction "2_2") (pintype "passive"))
      (node (ref "U6") (pin "5") (pinfunction "IO2_5") (pintype "bidirectional"))
      (node (ref "USB1") (pin "D+") (pinfunction "D+_D+") (pintype "bidirectional"))
    )
    (net (code "46") (name "MSP_D-") (class "Default")
      (node (ref "R22") (pin "2") (pinfunction "2_2") (pintype "passive"))
      (node (ref "U6") (pin "3") (pinfunction "IO1_3") (pintype "bidirectional"))
      (node (ref "USB1") (pin "D-") (pinfunction "D-_D-") (pintype "bidirectional"))
    )
    (net (code "47") (name "Net-(D1-PadC)") (class "Default")
      (node (ref "D1") (pin "C") (pinfunction "C_C") (pintype "passive"))
      (node (ref "JP15") (pin "2") (pinfunction "2_2") (pintype "passive"))
    )
    (net (code "48") (name "Net-(JP3-Pad2)") (class "Default")
      (node (ref "JP3") (pin "2") (pinfunction "2_2") (pintype "passive"))
      (node (ref "R3") (pin "1") (pinfunction "1_1") (pintype "passive"))
    )
    (net (code "49") (name "Net-(LED1-PadA)") (class "Default")
      (node (ref "LED1") (pin "A") (pinfunction "A_A") (pintype "passive"))
      (node (ref "R3") (pin "2") (pinfunction "2_2") (pintype "passive"))
    )
    (net (code "50") (name "Net-(LED2-PadA)") (class "Default")
      (node (ref "LED2") (pin "A") (pinfunction "A_A") (pintype "passive"))
      (node (ref "R4") (pin "2") (pinfunction "2_2") (pintype "passive"))
    )
    (net (code "51") (name "Net-(LED3-PadA)") (class "Default")
      (node (ref "LED3") (pin "A") (pinfunction "A_A") (pintype "passive"))
      (node (ref "R5") (pin "2") (pinfunction "2_2") (pintype "passive"))
    )
    (net (code "52") (name "Net-(LED4-PadA)") (class "Default")
      (node (ref "LED4") (pin "A") (pinfunction "A_A") (pintype "passive"))
      (node (ref "R7") (pin "2") (pinfunction "2_2") (pintype "passive"))
    )
    (net (code "53") (name "Net-(LED5-PadA)") (class "Default")
      (node (ref "LED5") (pin "A") (pinfunction "A_A") (pintype "passive"))
      (node (ref "R8") (pin "2") (pinfunction "2_2") (pintype "passive"))
    )
    (net (code "54") (name "Net-(LED6-PadA)") (class "Default")
      (node (ref "LED6") (pin "A") (pinfunction "A_A") (pintype "passive"))
      (node (ref "R9") (pin "2") (pinfunction "2_2") (pintype "passive"))
    )
    (net (code "55") (name "Net-(LED7-PadA)") (class "Default")
      (node (ref "LED7") (pin "A") (pinfunction "A_A") (pintype "passive"))
      (node (ref "R10") (pin "2") (pinfunction "2_2") (pintype "passive"))
    )
    (net (code "56") (name "Net-(LED8-PadA)") (class "Default")
      (node (ref "LED8") (pin "A") (pinfunction "A_A") (pintype "passive"))
      (node (ref "R11") (pin "2") (pinfunction "2_2") (pintype "passive"))
    )
    (net (code "57") (name "Net-(LED9-PadA)") (class "Default")
      (node (ref "LED9") (pin "A") (pinfunction "A_A") (pintype "passive"))
      (node (ref "R33") (pin "1") (pinfunction "1_1") (pintype "passive"))
    )
    (net (code "58") (name "Net-(POT1-CCW)") (class "Default")
      (node (ref "JP2") (pin "1") (pinfunction "1_1") (pintype "passive"))
      (node (ref "POT1") (pin "1") (pinfunction "CCW_1") (pintype "passive"))
    )
    (net (code "59") (name "Net-(Q3-1)") (class "Default")
      (node (ref "C38") (pin "1") (pinfunction "1_1") (pintype "passive"))
      (node (ref "Q3") (pin "P$1") (pinfunction "1_P$1") (pintype "passive"))
      (node (ref "U7") (pin "53") (pinfunction "53_53") (pintype "input"))
    )
    (net (code "60") (name "Net-(Q3-3)") (class "Default")
      (node (ref "C39") (pin "1") (pinfunction "1_1") (pintype "passive"))
      (node (ref "Q3") (pin "P$3") (pinfunction "3_P$3") (pintype "passive"))
      (node (ref "U7") (pin "52") (pinfunction "52_52") (pintype "output"))
    )
    (net (code "61") (name "Net-(R27-Pad2)") (class "Default")
      (node (ref "R27") (pin "2") (pinfunction "2_2") (pintype "passive"))
      (node (ref "USB1") (pin "GND@1") (pinfunction "GND_GND@1") (pintype "bidirectional"))
      (node (ref "USB1") (pin "GND@2") (pinfunction "GND_GND@2") (pintype "bidirectional"))
    )
    (net (code "62") (name "Net-(R29-Pad1)") (class "Default")
      (node (ref "R29") (pin "1") (pinfunction "1_1") (pintype "passive"))
      (node (ref "R31") (pin "1") (pinfunction "1_1") (pintype "passive"))
      (node (ref "U7") (pin "47") (pinfunction "47_47") (pintype "bidirectional"))
    )
    (net (code "63") (name "Net-(R30-Pad1)") (class "Default")
      (node (ref "R30") (pin "1") (pinfunction "1_1") (pintype "passive"))
      (node (ref "R32") (pin "1") (pinfunction "1_1") (pintype "passive"))
      (node (ref "U7") (pin "24") (pinfunction "24_24") (pintype "bidirectional"))
      (node (ref "U7") (pin "43") (pinfunction "43_43") (pintype "bidirectional"))
      (node (ref "U7") (pin "45") (pinfunction "45_45") (pintype "bidirectional"))
      (node (ref "U7") (pin "46") (pinfunction "46_46") (pintype "bidirectional"))
    )
    (net (code "64") (name "Net-(R48-Pad2)") (class "Default")
      (node (ref "R48") (pin "2") (pinfunction "2_2") (pintype "passive"))
      (node (ref "USB2") (pin "GND@1") (pinfunction "GND_GND@1") (pintype "bidirectional"))
      (node (ref "USB2") (pin "GND@2") (pinfunction "GND_GND@2") (pintype "bidirectional"))
    )
    (net (code "65") (name "Net-(S4-S)") (class "Default")
      (node (ref "R26") (pin "2") (pinfunction "2_2") (pintype "passive"))
      (node (ref "S4") (pin "2") (pinfunction "S_2") (pintype "passive"))
    )
    (net (code "66") (name "Net-(SW1-COM1)") (class "Default")
      (node (ref "J10") (pin "3") (pinfunction "3_3") (pintype "passive"))
      (node (ref "J9") (pin "1") (pinfunction "1_1") (pintype "bidirectional"))
      (node (ref "JP7") (pin "1") (pinfunction "1_1") (pintype "passive"))
      (node (ref "SW1") (pin "3") (pinfunction "COM1_3") (pintype "bidirectional"))
    )
    (net (code "67") (name "Net-(SW1-COM2)") (class "Default")
      (node (ref "JP6") (pin "1") (pinfunction "1_1") (pintype "passive"))
      (node (ref "SW1") (pin "7") (pinfunction "COM2_7") (pintype "bidirectional"))
    )
    (net (code "68") (name "Net-(TP3-TP)") (class "Default")
      (node (ref "CON1") (pin "2") (pinfunction "2_2") (pintype "bidirectional"))
      (node (ref "TP3") (pin "1") (pinfunction "TP_1") (pintype "input"))
    )
    (net (code "69") (name "Net-(TP4-TP)") (class "Default")
      (node (ref "CON1") (pin "1") (pinfunction "1_1") (pintype "bidirectional"))
      (node (ref "TP4") (pin "1") (pinfunction "TP_1") (pintype "input"))
    )
    (net (code "70") (name "Net-(TP5-TP)") (class "Default")
      (node (ref "CON1") (pin "4") (pinfunction "4_4") (pintype "bidirectional"))
      (node (ref "TP5") (pin "1") (pinfunction "TP_1") (pintype "input"))
    )
    (net (code "71") (name "Net-(TP6-TP)") (class "Default")
      (node (ref "CON1") (pin "3") (pinfunction "3_3") (pintype "bidirectional"))
      (node (ref "TP6") (pin "1") (pinfunction "TP_1") (pintype "input"))
    )
    (net (code "72") (name "Net-(TP7-TP)") (class "Default")
      (node (ref "CON1") (pin "6") (pinfunction "6_6") (pintype "bidirectional"))
      (node (ref "TP7") (pin "1") (pinfunction "TP_1") (pintype "input"))
    )
    (net (code "73") (name "Net-(TP8-TP)") (class "Default")
      (node (ref "CON1") (pin "7") (pinfunction "7_7") (pintype "bidirectional"))
      (node (ref "TP8") (pin "1") (pinfunction "TP_1") (pintype "input"))
    )
    (net (code "74") (name "Net-(U2-INT2)") (class "Default")
      (node (ref "R58") (pin "2") (pinfunction "2_2") (pintype "passive"))
      (node (ref "U2") (pin "9") (pinfunction "INT2_9") (pintype "output"))
    )
    (net (code "75") (name "Net-(U3-A1+|ARG)") (class "Default")
      (node (ref "U3") (pin "1") (pinfunction "A1+|ARG_1") (pintype "input"))
      (node (ref "U5") (pin "3") (pinfunction "D1A_3") (pintype "power_in"))
      (node (ref "U5") (pin "4") (pinfunction "D2A_4") (pintype "power_in"))
    )
    (net (code "76") (name "Net-(U3-A2+|NC)") (class "Default")
      (node (ref "U3") (pin "14") (pinfunction "A2+|NC_14") (pintype "input"))
      (node (ref "U5") (pin "7") (pinfunction "D2B_7") (pintype "power_in"))
      (node (ref "U5") (pin "8") (pinfunction "D1B_8") (pintype "power_in"))
    )
    (net (code "77") (name "Net-(U3-VB0+)") (class "Default")
      (node (ref "C26") (pin "2") (pinfunction "2_2") (pintype "passive"))
      (node (ref "U3") (pin "18") (pinfunction "VB0+_18") (pintype "passive"))
    )
    (net (code "78") (name "Net-(U3-VB0-)") (class "Default")
      (node (ref "C26") (pin "1") (pinfunction "1_1") (pintype "passive"))
      (node (ref "U3") (pin "17") (pinfunction "VB0-_17") (pintype "passive"))
    )
    (net (code "79") (name "Net-(U3-VB1+)") (class "Default")
      (node (ref "C25") (pin "2") (pinfunction "2_2") (pintype "passive"))
      (node (ref "U3") (pin "19") (pinfunction "VB1+_19") (pintype "passive"))
    )
    (net (code "80") (name "Net-(U3-VB1-)") (class "Default")
      (node (ref "C25") (pin "1") (pinfunction "1_1") (pintype "passive"))
      (node (ref "U3") (pin "16") (pinfunction "VB1-_16") (pintype "passive"))
    )
    (net (code "81") (name "Net-(U3-VLCD)") (class "Default")
      (node (ref "C22") (pin "1") (pinfunction "1_1") (pintype "passive"))
      (node (ref "U3") (pin "15") (pinfunction "VLCD_15") (pintype "passive"))
    )
    (net (code "82") (name "Net-(U4B-EN)") (class "Default")
      (node (ref "R19") (pin "1") (pinfunction "1_1") (pintype "passive"))
      (node (ref "U4") (pin "5") (pinfunction "EN_5") (pintype "input"))
    )
    (net (code "83") (name "Net-(U4B-NR{slash}FB)") (class "Default")
      (node (ref "C29") (pin "2") (pinfunction "2_2") (pintype "passive"))
      (node (ref "U4") (pin "3") (pinfunction "NR/FB_3") (pintype "passive"))
    )
    (net (code "84") (name "Net-(U5A-ISET)") (class "Default")
      (node (ref "R21") (pin "2") (pinfunction "2_2") (pintype "passive"))
      (node (ref "U5") (pin "10") (pinfunction "ISET_10") (pintype "input"))
    )
    (net (code "85") (name "Net-(U6-VCC)") (class "Default")
      (node (ref "D1") (pin "A") (pinfunction "A_A") (pintype "passive"))
      (node (ref "U6") (pin "1") (pinfunction "VCC_1") (pintype "power_in"))
      (node (ref "USB1") (pin "VBUS") (pinfunction "VBUS_VBUS") (pintype "bidirectional"))
    )
    (net (code "86") (name "Net-(U8-A1)") (class "Default")
      (node (ref "JP16") (pin "2") (pinfunction "2_2") (pintype "passive"))
      (node (ref "U8") (pin "2") (pinfunction "A1_2") (pintype "input"))
    )
    (net (code "87") (name "Net-(U8-A2)") (class "Default")
      (node (ref "JP16") (pin "4") (pinfunction "4_4") (pintype "passive"))
      (node (ref "U8") (pin "3") (pinfunction "A2_3") (pintype "input"))
    )
    (net (code "88") (name "Net-(U8-A3)") (class "Default")
      (node (ref "JP16") (pin "6") (pinfunction "6_6") (pintype "passive"))
      (node (ref "U8") (pin "4") (pinfunction "A3_4") (pintype "input"))
    )
    (net (code "89") (name "Net-(U8-A4)") (class "Default")
      (node (ref "JP16") (pin "8") (pinfunction "8_8") (pintype "passive"))
      (node (ref "U8") (pin "5") (pinfunction "A4_5") (pintype "input"))
    )
    (net (code "90") (name "Net-(U8-OE)") (class "Default")
      (node (ref "JP16") (pin "10") (pinfunction "10_10") (pintype "passive"))
      (node (ref "R34") (pin "2") (pinfunction "2_2") (pintype "passive"))
      (node (ref "U8") (pin "1") (pinfunction "VCCA_1") (pintype "power_in"))
      (node (ref "U8") (pin "8") (pinfunction "OE_8") (pintype "input"))
    )
    (net (code "91") (name "Net-(U9-FB)") (class "Default")
      (node (ref "R37") (pin "1") (pinfunction "1_1") (pintype "passive"))
      (node (ref "R38") (pin "2") (pinfunction "2_2") (pintype "passive"))
      (node (ref "U9") (pin "1") (pinfunction "FB_1") (pintype "input"))
    )
    (net (code "92") (name "Net-(U10-DM)") (class "Default")
      (node (ref "C46") (pin "2") (pinfunction "2_2") (pintype "passive"))
      (node (ref "R46") (pin "2") (pinfunction "2_2") (pintype "passive"))
      (node (ref "U10") (pin "7") (pinfunction "DM_7") (pintype "input"))
    )
    (net (code "93") (name "Net-(U10-DP)") (class "Default")
      (node (ref "C45") (pin "2") (pinfunction "2_2") (pintype "passive"))
      (node (ref "R42") (pin "1") (pinfunction "1_1") (pintype "passive"))
      (node (ref "R43") (pin "2") (pinfunction "2_2") (pintype "passive"))
      (node (ref "U10") (pin "6") (pinfunction "DP_6") (pintype "input"))
    )
    (net (code "94") (name "Net-(U10-PUR)") (class "Default")
      (node (ref "R42") (pin "2") (pinfunction "2_2") (pintype "passive"))
      (node (ref "U10") (pin "5") (pinfunction "PUR_5") (pintype "input"))
    )
    (net (code "95") (name "Net-(U10-SCL)") (class "Default")
      (node (ref "R52") (pin "2") (pinfunction "2_2") (pintype "passive"))
      (node (ref "U10") (pin "11") (pinfunction "SCL_11") (pintype "output"))
    )
    (net (code "96") (name "Net-(U10-SUSPEND)") (class "Default")
      (node (ref "D2") (pin "C") (pinfunction "C_C") (pintype "passive"))
      (node (ref "U10") (pin "2") (pinfunction "SUSPEND_2") (pintype "input"))
    )
    (net (code "97") (name "Net-(U10-VDD18)") (class "Default")
      (node (ref "R47") (pin "1") (pinfunction "1_1") (pintype "passive"))
      (node (ref "R50") (pin "2") (pinfunction "2_2") (pintype "passive"))
      (node (ref "U10") (pin "4") (pinfunction "VDD18_4") (pintype "power_in"))
    )
    (net (code "98") (name "Net-(U10-VREGEN)") (class "Default")
      (node (ref "D2") (pin "A") (pinfunction "A_A") (pintype "passive"))
      (node (ref "R41") (pin "1") (pinfunction "1_1") (pintype "passive"))
      (node (ref "U10") (pin "1") (pinfunction "VREGEN_1") (pintype "input"))
    )
    (net (code "99") (name "Net-(U10-WAKEUP)") (class "Default")
      (node (ref "R39") (pin "1") (pinfunction "1_1") (pintype "passive"))
      (node (ref "U10") (pin "12") (pinfunction "WAKEUP_12") (pintype "input"))
    )
    (net (code "100") (name "Net-(U10-X1)") (class "Default")
      (node (ref "R49") (pin "1") (pinfunction "1_1") (pintype "passive"))
      (node (ref "R51") (pin "1") (pinfunction "1_1") (pintype "passive"))
      (node (ref "U10") (pin "27") (pinfunction "X1_27") (pintype "input"))
    )
    (net (code "101") (name "P1.0") (class "Default")
      (node (ref "J12") (pin "3") (pinfunction "3_3") (pintype "passive"))
      (node (ref "JP3") (pin "1") (pinfunction "1_1") (pintype "passive"))
      (node (ref "RF2") (pin "13") (pinfunction "13_13") (pintype "passive"))
      (node (ref "U1") (pin "21") (pinfunction "21_21") (pintype "bidirectional"))
    )
    (net (code "102") (name "P1.1") (class "Default")
      (node (ref "R7") (pin "1") (pinfunction "1_1") (pintype "passive"))
      (node (ref "U1") (pin "22") (pinfunction "22_22") (pintype "bidirectional"))
    )
    (net (code "103") (name "P1.2") (class "Default")
      (node (ref "R8") (pin "1") (pinfunction "1_1") (pintype "passive"))
      (node (ref "U1") (pin "23") (pinfunction "23_23") (pintype "bidirectional"))
    )
    (net (code "104") (name "P1.3") (class "Default")
      (node (ref "R9") (pin "1") (pinfunction "1_1") (pintype "passive"))
      (node (ref "U1") (pin "24") (pinfunction "24_24") (pintype "bidirectional"))
    )
    (net (code "105") (name "P1.4") (class "Default")
      (node (ref "R10") (pin "1") (pinfunction "1_1") (pintype "passive"))
      (node (ref "U1") (pin "25") (pinfunction "25_25") (pintype "bidirectional"))
    )
    (net (code "106") (name "P1.5") (class "Default")
      (node (ref "R11") (pin "1") (pinfunction "1_1") (pintype "passive"))
      (node (ref "U1") (pin "26") (pinfunction "26_26") (pintype "bidirectional"))
    )
    (net (code "107") (name "P1.7") (class "Default")
      (node (ref "S1") (pin "1") (pinfunction "P_1") (pintype "passive"))
      (node (ref "U1") (pin "28") (pinfunction "28_28") (pintype "bidirectional"))
    )
    (net (code "108") (name "P2.0") (class "Default")
      (node (ref "J12") (pin "4") (pinfunction "4_4") (pintype "passive"))
      (node (ref "RF1") (pin "5") (pinfunction "5_5") (pintype "passive"))
      (node (ref "RF2") (pin "15") (pinfunction "15_15") (pintype "passive"))
      (node (ref "U1") (pin "29") (pinfunction "29_29") (pintype "bidirectional"))
    )
    (net (code "109") (name "P2.1") (class "Default")
      (node (ref "J12") (pin "14") (pinfunction "14_14") (pintype "passive"))
      (node (ref "R58") (pin "1") (pinfunction "1_1") (pintype "passive"))
      (node (ref "RF1") (pin "3") (pinfunction "3_3") (pintype "passive"))
      (node (ref "U1") (pin "30") (pinfunction "30_30") (pintype "bidirectional"))
    )
    (net (code "110") (name "P2.2") (class "Default")
      (node (ref "S2") (pin "1") (pinfunction "P_1") (pintype "passive"))
      (node (ref "U1") (pin "31") (pinfunction "31_31") (pintype "bidirectional"))
    )
    (net (code "111") (name "P2.3") (class "Default")
      (node (ref "J12") (pin "13") (pinfunction "13_13") (pintype "passive"))
      (node (ref "RF1") (pin "10") (pinfunction "10_10") (pintype "passive"))
      (node (ref "U1") (pin "32") (pinfunction "32_32") (pintype "bidirectional"))
    )
    (net (code "112") (name "P2.4") (class "Default")
      (node (ref "J12") (pin "10") (pinfunction "10_10") (pintype "passive"))
      (node (ref "RF1") (pin "12") (pinfunction "12_12") (pintype "passive"))
      (node (ref "U1") (pin "33") (pinfunction "33_33") (pintype "bidirectional"))
    )
    (net (code "113") (name "P4.0") (class "Default")
      (node (ref "J12") (pin "6") (pinfunction "6_6") (pintype "passive"))
      (node (ref "J5") (pin "9") (pinfunction "9_9") (pintype "passive"))
      (node (ref "RF1") (pin "6") (pinfunction "6_6") (pintype "passive"))
      (node (ref "RF1") (pin "7") (pinfunction "7_7") (pintype "passive"))
      (node (ref "U1") (pin "45") (pinfunction "45_45") (pintype "bidirectional"))
    )
    (net (code "114") (name "P4.6") (class "Default")
      (node (ref "CON3") (pin "2") (pinfunction "2_2") (pintype "bidirectional"))
      (node (ref "J12") (pin "8") (pinfunction "8_8") (pintype "passive"))
      (node (ref "J4") (pin "7") (pinfunction "7_7") (pintype "passive"))
      (node (ref "RF1") (pin "8") (pinfunction "8_8") (pintype "passive"))
      (node (ref "RF1") (pin "9") (pinfunction "9_9") (pintype "passive"))
      (node (ref "U1") (pin "53") (pinfunction "53_53") (pintype "bidirectional"))
    )
    (net (code "115") (name "P4.7") (class "Default")
      (node (ref "CON3") (pin "1") (pinfunction "1_1") (pintype "bidirectional"))
      (node (ref "J12") (pin "9") (pinfunction "9_9") (pintype "passive"))
      (node (ref "J4") (pin "9") (pinfunction "9_9") (pintype "passive"))
      (node (ref "RF2") (pin "18") (pinfunction "18_18") (pintype "passive"))
      (node (ref "U1") (pin "54") (pinfunction "54_54") (pintype "bidirectional"))
    )
    (net (code "116") (name "P5.1") (class "Default")
      (node (ref "J4") (pin "11") (pinfunction "11_11") (pintype "passive"))
      (node (ref "U1") (pin "10") (pinfunction "10_10") (pintype "bidirectional"))
    )
    (net (code "117") (name "P6.6") (class "Default")
      (node (ref "J4") (pin "2") (pinfunction "2_2") (pintype "passive"))
      (node (ref "RF2") (pin "20") (pinfunction "20_20") (pintype "passive"))
      (node (ref "U1") (pin "3") (pinfunction "3_3") (pintype "bidirectional"))
    )
    (net (code "118") (name "P6.7") (class "Default")
      (node (ref "J4") (pin "14") (pinfunction "14_14") (pintype "passive"))
      (node (ref "U1") (pin "4") (pinfunction "4_4") (pintype "bidirectional"))
    )
    (net (code "119") (name "P7.0") (class "Default")
      (node (ref "J5") (pin "2") (pinfunction "2_2") (pintype "passive"))
      (node (ref "U1") (pin "5") (pinfunction "5_5") (pintype "bidirectional"))
    )
    (net (code "120") (name "P7.1") (class "Default")
      (node (ref "J5") (pin "4") (pinfunction "4_4") (pintype "passive"))
      (node (ref "U1") (pin "6") (pinfunction "6_6") (pintype "bidirectional"))
    )
    (net (code "121") (name "P7.2") (class "Default")
      (node (ref "J5") (pin "6") (pinfunction "6_6") (pintype "passive"))
      (node (ref "U1") (pin "7") (pinfunction "7_7") (pintype "bidirectional"))
    )
    (net (code "122") (name "P7.3") (class "Default")
      (node (ref "J5") (pin "8") (pinfunction "8_8") (pintype "passive"))
      (node (ref "U1") (pin "8") (pinfunction "8_8") (pintype "bidirectional"))
    )
    (net (code "123") (name "P7.5") (class "Default")
      (node (ref "J12") (pin "11") (pinfunction "11_11") (pintype "passive"))
      (node (ref "RF2") (pin "19") (pinfunction "19_19") (pintype "passive"))
      (node (ref "U1") (pin "58") (pinfunction "58_58") (pintype "bidirectional"))
    )
    (net (code "124") (name "P7.7") (class "Default")
      (node (ref "J5") (pin "14") (pinfunction "14_14") (pintype "passive"))
      (node (ref "U1") (pin "60") (pinfunction "60_60") (pintype "bidirectional"))
    )
    (net (code "125") (name "P8.0") (class "Default")
      (node (ref "J4") (pin "8") (pinfunction "8_8") (pintype "passive"))
      (node (ref "JP2") (pin "2") (pinfunction "2_2") (pintype "passive"))
      (node (ref "U1") (pin "15") (pinfunction "15_15") (pintype "bidirectional"))
    )
    (net (code "126") (name "P8.1") (class "Default")
      (node (ref "J4") (pin "4") (pinfunction "4_4") (pintype "passive"))
      (node (ref "R4") (pin "1") (pinfunction "1_1") (pintype "passive"))
      (node (ref "U1") (pin "16") (pinfunction "16_16") (pintype "bidirectional"))
    )
    (net (code "127") (name "P8.2") (class "Default")
      (node (ref "J4") (pin "6") (pinfunction "6_6") (pintype "passive"))
      (node (ref "R5") (pin "1") (pinfunction "1_1") (pintype "passive"))
      (node (ref "U1") (pin "17") (pinfunction "17_17") (pintype "bidirectional"))
    )
    (net (code "128") (name "PU.0{slash}DP") (class "Default")
      (node (ref "C36") (pin "1") (pinfunction "1_1") (pintype "passive"))
      (node (ref "R23") (pin "1") (pinfunction "1_1") (pintype "passive"))
      (node (ref "R24") (pin "2") (pinfunction "2_2") (pintype "passive"))
      (node (ref "R25") (pin "2") (pinfunction "2_2") (pintype "passive"))
      (node (ref "U1") (pin "62") (pinfunction "62_62") (pintype "bidirectional"))
    )
    (net (code "129") (name "PU.1{slash}DM") (class "Default")
      (node (ref "C35") (pin "1") (pinfunction "1_1") (pintype "passive"))
      (node (ref "R22") (pin "1") (pinfunction "1_1") (pintype "passive"))
      (node (ref "U1") (pin "64") (pinfunction "64_64") (pintype "bidirectional"))
    )
    (net (code "130") (name "PUR") (class "Default")
      (node (ref "R25") (pin "1") (pinfunction "1_1") (pintype "passive"))
      (node (ref "R26") (pin "1") (pinfunction "1_1") (pintype "passive"))
      (node (ref "U1") (pin "63") (pinfunction "63_63") (pintype "bidirectional"))
    )
    (net (code "131") (name "RESET") (class "Default")
      (node (ref "C37") (pin "1") (pinfunction "1_1") (pintype "passive"))
      (node (ref "R28") (pin "1") (pinfunction "1_1") (pintype "passive"))
      (node (ref "TP10") (pin "1") (pinfunction "1_1") (pintype "passive"))
      (node (ref "U7") (pin "58") (pinfunction "58_58") (pintype "input"))
      (node (ref "U9") (pin "2") (pinfunction "RES_2") (pintype "output"))
    )
    (net (code "132") (name "RF_PWR") (class "Default")
      (node (ref "C31") (pin "1") (pinfunction "1_1") (pintype "passive"))
      (node (ref "C32") (pin "1") (pinfunction "1_1") (pintype "passive"))
      (node (ref "J12") (pin "2") (pinfunction "2_2") (pintype "passive"))
      (node (ref "J13") (pin "2") (pinfunction "2_2") (pintype "bidirectional"))
      (node (ref "JP14") (pin "2") (pinfunction "2_2") (pintype "passive"))
      (node (ref "RF2") (pin "7") (pinfunction "7_7") (pintype "passive"))
      (node (ref "RF2") (pin "9") (pinfunction "9_9") (pintype "passive"))
    )
    (net (code "133") (name "RF_SIMO") (class "Default")
      (node (ref "J12") (pin "18") (pinfunction "18_18") (pintype "passive"))
      (node (ref "RF1") (pin "18") (pinfunction "18_18") (pintype "passive"))
      (node (ref "U1") (pin "37") (pinfunction "37_37") (pintype "bidirectional"))
    )
    (net (code "134") (name "RF_SOMI") (class "Default")
      (node (ref "J12") (pin "15") (pinfunction "15_15") (pintype "passive"))
      (node (ref "RF1") (pin "20") (pinfunction "20_20") (pintype "passive"))
      (node (ref "U1") (pin "38") (pinfunction "38_38") (pintype "bidirectional"))
    )
    (net (code "135") (name "RF_SPI_CLK") (class "Default")
      (node (ref "J12") (pin "16") (pinfunction "16_16") (pintype "passive"))
      (node (ref "RF1") (pin "16") (pinfunction "16_16") (pintype "passive"))
      (node (ref "U1") (pin "39") (pinfunction "39_39") (pintype "bidirectional"))
    )
    (net (code "136") (name "RF_STE") (class "Default")
      (node (ref "J12") (pin "17") (pinfunction "17_17") (pintype "passive"))
      (node (ref "RF1") (pin "14") (pinfunction "14_14") (pintype "passive"))
      (node (ref "U1") (pin "35") (pinfunction "35_35") (pintype "bidirectional"))
    )
    (net (code "137") (name "RST3410") (class "Default")
      (node (ref "C44") (pin "1") (pinfunction "1_1") (pintype "passive"))
      (node (ref "R40") (pin "1") (pinfunction "1_1") (pintype "passive"))
      (node (ref "R41") (pin "2") (pinfunction "2_2") (pintype "passive"))
      (node (ref "U10") (pin "9") (pinfunction "RESET_9") (pintype "input"))
      (node (ref "U7") (pin "42") (pinfunction "42_42") (pintype "bidirectional"))
    )
    (net (code "138") (name "RST{slash}NMI") (class "Default")
      (node (ref "C3") (pin "2") (pinfunction "2_2") (pintype "passive"))
      (node (ref "J1") (pin "11") (pinfunction "11_11") (pintype "passive"))
      (node (ref "JP16") (pin "3") (pinfunction "3_3") (pintype "passive"))
      (node (ref "R1") (pin "1") (pinfunction "1_1") (pintype "passive"))
      (node (ref "S3") (pin "1") (pinfunction "P_1") (pintype "passive"))
      (node (ref "U1") (pin "76") (pinfunction "76_76") (pintype "bidirectional"))
    )
    (net (code "139") (name "RXD") (class "Default")
      (node (ref "CON1") (pin "8") (pinfunction "8_8") (pintype "bidirectional"))
      (node (ref "J12") (pin "7") (pinfunction "7_7") (pintype "passive"))
      (node (ref "J13") (pin "6") (pinfunction "6_6") (pintype "bidirectional"))
      (node (ref "J4") (pin "10") (pinfunction "10_10") (pintype "passive"))
      (node (ref "J4") (pin "3") (pinfunction "3_3") (pintype "passive"))
      (node (ref "JP16") (pin "5") (pinfunction "5_5") (pintype "passive"))
      (node (ref "U1") (pin "52") (pinfunction "52_52") (pintype "bidirectional"))
    )
    (net (code "140") (name "SBWTCK") (class "Default")
      (node (ref "J17") (pin "3") (pinfunction "3_3") (pintype "passive"))
      (node (ref "R31") (pin "2") (pinfunction "2_2") (pintype "passive"))
      (node (ref "U8") (pin "13") (pinfunction "B1_13") (pintype "output"))
    )
    (net (code "141") (name "SBWTDIO") (class "Default")
      (node (ref "J17") (pin "4") (pinfunction "4_4") (pintype "passive"))
      (node (ref "R32") (pin "2") (pinfunction "2_2") (pintype "passive"))
      (node (ref "U8") (pin "12") (pinfunction "B2_12") (pintype "output"))
    )
    (net (code "142") (name "SCL") (class "Default")
      (node (ref "R52") (pin "1") (pinfunction "1_1") (pintype "passive"))
      (node (ref "R54") (pin "2") (pinfunction "2_2") (pintype "passive"))
      (node (ref "U12") (pin "6") (pinfunction "SCL_6") (pintype "power_in"))
      (node (ref "U7") (pin "31") (pinfunction "31_31") (pintype "bidirectional"))
    )
    (net (code "143") (name "SCLK") (class "Default")
      (node (ref "J5") (pin "7") (pinfunction "7_7") (pintype "passive"))
      (node (ref "U1") (pin "48") (pinfunction "48_48") (pintype "bidirectional"))
      (node (ref "U3") (pin "25") (pinfunction "SCK_25") (pintype "bidirectional"))
      (node (ref "X1") (pin "5") (pinfunction "CLK_5") (pintype "bidirectional"))
    )
    (net (code "144") (name "SDA") (class "Default")
      (node (ref "R53") (pin "2") (pinfunction "2_2") (pintype "passive"))
      (node (ref "U10") (pin "10") (pinfunction "SDA_10") (pintype "bidirectional"))
      (node (ref "U12") (pin "5") (pinfunction "SDA_5") (pintype "power_in"))
      (node (ref "U7") (pin "29") (pinfunction "29_29") (pintype "bidirectional"))
    )
    (net (code "145") (name "SD_CS") (class "Default")
      (node (ref "J5") (pin "11") (pinfunction "11_11") (pintype "passive"))
      (node (ref "R6") (pin "2") (pinfunction "2_2") (pintype "passive"))
      (node (ref "U1") (pin "44") (pinfunction "44_44") (pintype "bidirectional"))
      (node (ref "X1") (pin "2") (pinfunction "DAT3_2") (pintype "bidirectional"))
    )
    (net (code "146") (name "SIMO") (class "Default")
      (node (ref "J5") (pin "10") (pinfunction "10_10") (pintype "passive"))
      (node (ref "J5") (pin "5") (pinfunction "5_5") (pintype "passive"))
      (node (ref "U1") (pin "46") (pinfunction "46_46") (pintype "bidirectional"))
      (node (ref "U3") (pin "24") (pinfunction "SDA_24") (pintype "bidirectional"))
      (node (ref "X1") (pin "3") (pinfunction "CMD_3") (pintype "bidirectional"))
    )
    (net (code "147") (name "SOMI") (class "Default")
      (node (ref "J5") (pin "12") (pinfunction "12_12") (pintype "passive"))
      (node (ref "J5") (pin "3") (pinfunction "3_3") (pintype "passive"))
      (node (ref "U1") (pin "47") (pinfunction "47_47") (pintype "bidirectional"))
      (node (ref "X1") (pin "7") (pinfunction "DAT0_7") (pintype "bidirectional"))
    )
    (net (code "148") (name "TCK") (class "Default")
      (node (ref "J1") (pin "7") (pinfunction "7_7") (pintype "passive"))
      (node (ref "U1") (pin "75") (pinfunction "75_75") (pintype "bidirectional"))
    )
    (net (code "149") (name "TDI") (class "Default")
      (node (ref "J1") (pin "3") (pinfunction "3_3") (pintype "passive"))
      (node (ref "U1") (pin "73") (pinfunction "73_73") (pintype "bidirectional"))
    )
    (net (code "150") (name "TDO") (class "Default")
      (node (ref "J1") (pin "1") (pinfunction "1_1") (pintype "passive"))
      (node (ref "U1") (pin "72") (pinfunction "72_72") (pintype "bidirectional"))
    )
    (net (code "151") (name "TEST") (class "Default")
      (node (ref "J1") (pin "8") (pinfunction "8_8") (pintype "passive"))
      (node (ref "JP16") (pin "1") (pinfunction "1_1") (pintype "passive"))
      (node (ref "U1") (pin "71") (pinfunction "71_71") (pintype "input"))
    )
    (net (code "152") (name "TMS") (class "Default")
      (node (ref "J1") (pin "5") (pinfunction "5_5") (pintype "passive"))
      (node (ref "U1") (pin "74") (pinfunction "74_74") (pintype "bidirectional"))
    )
    (net (code "153") (name "TXD") (class "Default")
      (node (ref "CON1") (pin "5") (pinfunction "5_5") (pintype "bidirectional"))
      (node (ref "J12") (pin "5") (pinfunction "5_5") (pintype "passive"))
      (node (ref "J13") (pin "1") (pinfunction "1_1") (pintype "bidirectional"))
      (node (ref "J4") (pin "12") (pinfunction "12_12") (pintype "passive"))
      (node (ref "J4") (pin "5") (pinfunction "5_5") (pintype "passive"))
      (node (ref "JP16") (pin "7") (pinfunction "7_7") (pintype "passive"))
      (node (ref "U1") (pin "51") (pinfunction "51_51") (pintype "bidirectional"))
    )
    (net (code "154") (name "UCTS") (class "Default")
      (node (ref "U10") (pin "13") (pinfunction "CTS_13") (pintype "input"))
      (node (ref "U7") (pin "18") (pinfunction "18_18") (pintype "bidirectional"))
    )
    (net (code "155") (name "UDSR") (class "Default")
      (node (ref "U10") (pin "14") (pinfunction "DSR_14") (pintype "input"))
      (node (ref "U7") (pin "17") (pinfunction "17_17") (pintype "bidirectional"))
    )
    (net (code "156") (name "UDTR") (class "Default")
      (node (ref "U10") (pin "21") (pinfunction "DTR_21") (pintype "input"))
      (node (ref "U7") (pin "16") (pinfunction "16_16") (pintype "bidirectional"))
    )
    (net (code "157") (name "URTS") (class "Default")
      (node (ref "U10") (pin "20") (pinfunction "RTS_20") (pintype "input"))
      (node (ref "U7") (pin "15") (pinfunction "15_15") (pintype "bidirectional"))
    )
    (net (code "158") (name "URXD") (class "Default")
      (node (ref "U10") (pin "19") (pinfunction "SOUT_19") (pintype "output"))
      (node (ref "U7") (pin "33") (pinfunction "33_33") (pintype "bidirectional"))
    )
    (net (code "159") (name "UTXD") (class "Default")
      (node (ref "U10") (pin "17") (pinfunction "SIN_17") (pintype "input"))
      (node (ref "U7") (pin "32") (pinfunction "32_32") (pintype "bidirectional"))
    )
    (net (code "160") (name "V18") (class "Default")
      (node (ref "C8") (pin "1") (pinfunction "1_1") (pintype "passive"))
      (node (ref "U1") (pin "67") (pinfunction "67_67") (pintype "power_in"))
    )
    (net (code "161") (name "VCC") (class "Default")
      (node (ref "C18") (pin "2") (pinfunction "2_2") (pintype "passive"))
      (node (ref "C19") (pin "2") (pinfunction "2_2") (pintype "passive"))
      (node (ref "C23") (pin "2") (pinfunction "2_2") (pintype "passive"))
      (node (ref "C24") (pin "2") (pinfunction "2_2") (pintype "passive"))
      (node (ref "C30") (pin "2") (pinfunction "2_2") (pintype "passive"))
      (node (ref "CON2") (pin "2") (pinfunction "2_2") (pintype "bidirectional"))
      (node (ref "CON2") (pin "4") (pinfunction "4_4") (pintype "bidirectional"))
      (node (ref "J4") (pin "1") (pinfunction "1_1") (pintype "passive"))
      (node (ref "J5") (pin "1") (pinfunction "1_1") (pintype "passive"))
      (node (ref "JP14") (pin "1") (pinfunction "1_1") (pintype "passive"))
      (node (ref "JP7") (pin "2") (pinfunction "2_2") (pintype "passive"))
      (node (ref "R17") (pin "1") (pinfunction "1_1") (pintype "passive"))
      (node (ref "R18") (pin "1") (pinfunction "1_1") (pintype "passive"))
      (node (ref "R6") (pin "1") (pinfunction "1_1") (pintype "passive"))
      (node (ref "U3") (pin "22") (pinfunction "VDD2/3_22") (pintype "power_in"))
      (node (ref "U3") (pin "23") (pinfunction "VDD1_23") (pintype "power_in"))
      (node (ref "U5") (pin "9") (pinfunction "VIN_9") (pintype "power_in"))
      (node (ref "X1") (pin "4") (pinfunction "VDD_4") (pintype "bidirectional"))
    )
    (net (code "162") (name "VCORE") (class "Default")
      (node (ref "C17") (pin "2") (pinfunction "2_2") (pintype "passive"))
      (node (ref "TP2") (pin "1") (pinfunction "TP_1") (pintype "input"))
      (node (ref "U1") (pin "20") (pinfunction "20_20") (pintype "power_in"))
    )
    (net (code "163") (name "VREF+") (class "Default")
      (node (ref "C14") (pin "2") (pinfunction "2_2") (pintype "passive"))
      (node (ref "TP1") (pin "1") (pinfunction "TP_1") (pintype "input"))
      (node (ref "U1") (pin "9") (pinfunction "9_9") (pintype "bidirectional"))
    )
    (net (code "164") (name "XIN") (class "Default")
      (node (ref "C2") (pin "1") (pinfunction "1_1") (pintype "passive"))
      (node (ref "Q1") (pin "P2") (pinfunction "2_P2") (pintype "bidirectional"))
      (node (ref "U1") (pin "12") (pinfunction "12_12") (pintype "bidirectional"))
    )
    (net (code "165") (name "XOUT") (class "Default")
      (node (ref "C4") (pin "1") (pinfunction "1_1") (pintype "passive"))
      (node (ref "Q1") (pin "P1") (pinfunction "1_P1") (pintype "bidirectional"))
      (node (ref "U1") (pin "13") (pinfunction "13_13") (pintype "bidirectional"))
    )
    (net (code "166") (name "XT2GND") (class "Default")
      (node (ref "C1") (pin "2") (pinfunction "2_2") (pintype "passive"))
      (node (ref "C6") (pin "2") (pinfunction "2_2") (pintype "passive"))
    )
    (net (code "167") (name "XT2IN") (class "Default")
      (node (ref "C6") (pin "1") (pinfunction "1_1") (pintype "passive"))
      (node (ref "Q2") (pin "1") (pinfunction "1_1") (pintype "bidirectional"))
      (node (ref "Q2") (pin "1.1") (pinfunction "1.1_1.1") (pintype "bidirectional"))
      (node (ref "U1") (pin "69") (pinfunction "69_69") (pintype "bidirectional"))
    )
    (net (code "168") (name "XT2OUT") (class "Default")
      (node (ref "C1") (pin "1") (pinfunction "1_1") (pintype "passive"))
      (node (ref "Q2") (pin "2") (pinfunction "2_2") (pintype "bidirectional"))
      (node (ref "Q2") (pin "2.1") (pinfunction "2.1_2.1") (pintype "bidirectional"))
      (node (ref "U1") (pin "70") (pinfunction "70_70") (pintype "bidirectional"))
    )
    (net (code "169") (name "unconnected-(CON2-Pad1)") (class "Default")
      (node (ref "CON2") (pin "1") (pinfunction "1_1") (pintype "bidirectional"))
    )
    (net (code "170") (name "unconnected-(CON2-Pad3)") (class "Default")
      (node (ref "CON2") (pin "3") (pinfunction "3_3") (pintype "bidirectional"))
    )
    (net (code "171") (name "unconnected-(CON2-Pad5)") (class "Default")
      (node (ref "CON2") (pin "5") (pinfunction "5_5") (pintype "bidirectional"))
    )
    (net (code "172") (name "unconnected-(CON2-Pad6)") (class "Default")
      (node (ref "CON2") (pin "6") (pinfunction "6_6") (pintype "bidirectional"))
    )
    (net (code "173") (name "unconnected-(CON3-Pad3)") (class "Default")
      (node (ref "CON3") (pin "3") (pinfunction "3_3") (pintype "bidirectional"))
    )
    (net (code "174") (name "unconnected-(CON3-Pad4)") (class "Default")
      (node (ref "CON3") (pin "4") (pinfunction "4_4") (pintype "bidirectional"))
    )
    (net (code "175") (name "unconnected-(CON3-Pad5)") (class "Default")
      (node (ref "CON3") (pin "5") (pinfunction "5_5") (pintype "bidirectional"))
    )
    (net (code "176") (name "unconnected-(CON3-Pad6)") (class "Default")
      (node (ref "CON3") (pin "6") (pinfunction "6_6") (pintype "bidirectional"))
    )
    (net (code "177") (name "unconnected-(CON3-Pad7)") (class "Default")
      (node (ref "CON3") (pin "7") (pinfunction "7_7") (pintype "bidirectional"))
    )
    (net (code "178") (name "unconnected-(CON3-Pad8)") (class "Default")
      (node (ref "CON3") (pin "8") (pinfunction "8_8") (pintype "bidirectional"))
    )
    (net (code "179") (name "unconnected-(J1-Pad6)") (class "Default")
      (node (ref "J1") (pin "6") (pinfunction "6_6") (pintype "passive"))
    )
    (net (code "180") (name "unconnected-(J1-Pad10)") (class "Default")
      (node (ref "J1") (pin "10") (pinfunction "10_10") (pintype "passive"))
    )
    (net (code "181") (name "unconnected-(J1-Pad12)") (class "Default")
      (node (ref "J1") (pin "12") (pinfunction "12_12") (pintype "passive"))
    )
    (net (code "182") (name "unconnected-(J1-Pad13)") (class "Default")
      (node (ref "J1") (pin "13") (pinfunction "13_13") (pintype "passive"))
    )
    (net (code "183") (name "unconnected-(J1-Pad14)") (class "Default")
      (node (ref "J1") (pin "14") (pinfunction "14_14") (pintype "passive"))
    )
    (net (code "184") (name "unconnected-(J13-Pad3)") (class "Default")
      (node (ref "J13") (pin "3") (pinfunction "3_3") (pintype "bidirectional"))
    )
    (net (code "185") (name "unconnected-(J13-Pad4)") (class "Default")
      (node (ref "J13") (pin "4") (pinfunction "4_4") (pintype "bidirectional"))
    )
    (net (code "186") (name "unconnected-(JP11-Pad3)") (class "Default")
      (node (ref "JP11") (pin "3") (pinfunction "3_3") (pintype "passive"))
    )
    (net (code "187") (name "unconnected-(Q3-G2-PadP$2)") (class "Default")
      (node (ref "Q3") (pin "P$2") (pinfunction "G2_P$2") (pintype "bidirectional"))
    )
    (net (code "188") (name "unconnected-(Q3-G4-PadP$4)") (class "Default")
      (node (ref "Q3") (pin "P$4") (pinfunction "G4_P$4") (pintype "bidirectional"))
    )
    (net (code "189") (name "unconnected-(RF1-Pad2)") (class "Default")
      (node (ref "RF1") (pin "2") (pinfunction "2_2") (pintype "passive"))
    )
    (net (code "190") (name "unconnected-(RF1-Pad4)") (class "Default")
      (node (ref "RF1") (pin "4") (pinfunction "4_4") (pintype "passive"))
    )
    (net (code "191") (name "unconnected-(RF1-Pad11)") (class "Default")
      (node (ref "RF1") (pin "11") (pinfunction "11_11") (pintype "passive"))
    )
    (net (code "192") (name "unconnected-(RF1-Pad13)") (class "Default")
      (node (ref "RF1") (pin "13") (pinfunction "13_13") (pintype "passive"))
    )
    (net (code "193") (name "unconnected-(RF1-Pad15)") (class "Default")
      (node (ref "RF1") (pin "15") (pinfunction "15_15") (pintype "passive"))
    )
    (net (code "194") (name "unconnected-(RF1-Pad17)") (class "Default")
      (node (ref "RF1") (pin "17") (pinfunction "17_17") (pintype "passive"))
    )
    (net (code "195") (name "unconnected-(RF2-Pad1)") (class "Default")
      (node (ref "RF2") (pin "1") (pinfunction "1_1") (pintype "passive"))
    )
    (net (code "196") (name "unconnected-(RF2-Pad3)") (class "Default")
      (node (ref "RF2") (pin "3") (pinfunction "3_3") (pintype "passive"))
    )
    (net (code "197") (name "unconnected-(RF2-Pad4)") (class "Default")
      (node (ref "RF2") (pin "4") (pinfunction "4_4") (pintype "passive"))
    )
    (net (code "198") (name "unconnected-(RF2-Pad5)") (class "Default")
      (node (ref "RF2") (pin "5") (pinfunction "5_5") (pintype "passive"))
    )
    (net (code "199") (name "unconnected-(RF2-Pad6)") (class "Default")
      (node (ref "RF2") (pin "6") (pinfunction "6_6") (pintype "passive"))
    )
    (net (code "200") (name "unconnected-(RF2-Pad8)") (class "Default")
      (node (ref "RF2") (pin "8") (pinfunction "8_8") (pintype "passive"))
    )
    (net (code "201") (name "unconnected-(RF2-Pad10)") (class "Default")
      (node (ref "RF2") (pin "10") (pinfunction "10_10") (pintype "passive"))
    )
    (net (code "202") (name "unconnected-(RF2-Pad11)") (class "Default")
      (node (ref "RF2") (pin "11") (pinfunction "11_11") (pintype "passive"))
    )
    (net (code "203") (name "unconnected-(RF2-Pad12)") (class "Default")
      (node (ref "RF2") (pin "12") (pinfunction "12_12") (pintype "passive"))
    )
    (net (code "204") (name "unconnected-(RF2-Pad14)") (class "Default")
      (node (ref "RF2") (pin "14") (pinfunction "14_14") (pintype "passive"))
    )
    (net (code "205") (name "unconnected-(RF2-Pad16)") (class "Default")
      (node (ref "RF2") (pin "16") (pinfunction "16_16") (pintype "passive"))
    )
    (net (code "206") (name "unconnected-(RF2-Pad17)") (class "Default")
      (node (ref "RF2") (pin "17") (pinfunction "17_17") (pintype "passive"))
    )
    (net (code "207") (name "unconnected-(U2-ADC1-Pad16)") (class "Default")
      (node (ref "U2") (pin "16") (pinfunction "ADC1_16") (pintype "input"))
    )
    (net (code "208") (name "unconnected-(U2-ADC2-Pad15)") (class "Default")
      (node (ref "U2") (pin "15") (pinfunction "ADC2_15") (pintype "input"))
    )
    (net (code "209") (name "unconnected-(U2-ADC3-Pad13)") (class "Default")
      (node (ref "U2") (pin "13") (pinfunction "ADC3_13") (pintype "input"))
    )
    (net (code "210") (name "unconnected-(U2-NC_1-Pad3)") (class "Default")
      (node (ref "U2") (pin "3") (pinfunction "NC_1_3") (pintype "no_connect"))
    )
    (net (code "211") (name "unconnected-(U2-NC_2-Pad2)") (class "Default")
      (node (ref "U2") (pin "2") (pinfunction "NC_2_2") (pintype "no_connect"))
    )
    (net (code "212") (name "unconnected-(U6-NC-Pad2)") (class "Default")
      (node (ref "U6") (pin "2") (pinfunction "NC_2") (pintype "no_connect"))
    )
    (net (code "213") (name "unconnected-(U7-Pad2)") (class "Default")
      (node (ref "U7") (pin "2") (pinfunction "2_2") (pintype "bidirectional"))
    )
    (net (code "214") (name "unconnected-(U7-Pad3)") (class "Default")
      (node (ref "U7") (pin "3") (pinfunction "3_3") (pintype "bidirectional"))
    )
    (net (code "215") (name "unconnected-(U7-Pad4)") (class "Default")
      (node (ref "U7") (pin "4") (pinfunction "4_4") (pintype "bidirectional"))
    )
    (net (code "216") (name "unconnected-(U7-Pad5)") (class "Default")
      (node (ref "U7") (pin "5") (pinfunction "5_5") (pintype "bidirectional"))
    )
    (net (code "217") (name "unconnected-(U7-Pad6)") (class "Default")
      (node (ref "U7") (pin "6") (pinfunction "6_6") (pintype "bidirectional"))
    )
    (net (code "218") (name "unconnected-(U7-Pad7)") (class "Default")
      (node (ref "U7") (pin "7") (pinfunction "7_7") (pintype "output"))
    )
    (net (code "219") (name "unconnected-(U7-Pad8)") (class "Default")
      (node (ref "U7") (pin "8") (pinfunction "8_8") (pintype "input"))
    )
    (net (code "220") (name "unconnected-(U7-Pad9)") (class "Default")
      (node (ref "U7") (pin "9") (pinfunction "9_9") (pintype "bidirectional"))
    )
    (net (code "221") (name "unconnected-(U7-Pad10)") (class "Default")
      (node (ref "U7") (pin "10") (pinfunction "10_10") (pintype "input"))
    )
    (net (code "222") (name "unconnected-(U7-Pad11)") (class "Default")
      (node (ref "U7") (pin "11") (pinfunction "11_11") (pintype "bidirectional"))
    )
    (net (code "223") (name "unconnected-(U7-Pad12)") (class "Default")
      (node (ref "U7") (pin "12") (pinfunction "12_12") (pintype "bidirectional"))
    )
    (net (code "224") (name "unconnected-(U7-Pad13)") (class "Default")
      (node (ref "U7") (pin "13") (pinfunction "13_13") (pintype "bidirectional"))
    )
    (net (code "225") (name "unconnected-(U7-Pad14)") (class "Default")
      (node (ref "U7") (pin "14") (pinfunction "14_14") (pintype "bidirectional"))
    )
    (net (code "226") (name "unconnected-(U7-Pad19)") (class "Default")
      (node (ref "U7") (pin "19") (pinfunction "19_19") (pintype "bidirectional"))
    )
    (net (code "227") (name "unconnected-(U7-Pad20)") (class "Default")
      (node (ref "U7") (pin "20") (pinfunction "20_20") (pintype "bidirectional"))
    )
    (net (code "228") (name "unconnected-(U7-Pad21)") (class "Default")
      (node (ref "U7") (pin "21") (pinfunction "21_21") (pintype "bidirectional"))
    )
    (net (code "229") (name "unconnected-(U7-Pad22)") (class "Default")
      (node (ref "U7") (pin "22") (pinfunction "22_22") (pintype "bidirectional"))
    )
    (net (code "230") (name "unconnected-(U7-Pad23)") (class "Default")
      (node (ref "U7") (pin "23") (pinfunction "23_23") (pintype "bidirectional"))
    )
    (net (code "231") (name "unconnected-(U7-Pad25)") (class "Default")
      (node (ref "U7") (pin "25") (pinfunction "25_25") (pintype "bidirectional"))
    )
    (net (code "232") (name "unconnected-(U7-Pad26)") (class "Default")
      (node (ref "U7") (pin "26") (pinfunction "26_26") (pintype "bidirectional"))
    )
    (net (code "233") (name "unconnected-(U7-Pad27)") (class "Default")
      (node (ref "U7") (pin "27") (pinfunction "27_27") (pintype "bidirectional"))
    )
    (net (code "234") (name "unconnected-(U7-Pad28)") (class "Default")
      (node (ref "U7") (pin "28") (pinfunction "28_28") (pintype "bidirectional"))
    )
    (net (code "235") (name "unconnected-(U7-Pad30)") (class "Default")
      (node (ref "U7") (pin "30") (pinfunction "30_30") (pintype "bidirectional"))
    )
    (net (code "236") (name "unconnected-(U7-Pad36)") (class "Default")
      (node (ref "U7") (pin "36") (pinfunction "36_36") (pintype "output"))
    )
    (net (code "237") (name "unconnected-(U7-Pad37)") (class "Default")
      (node (ref "U7") (pin "37") (pinfunction "37_37") (pintype "bidirectional"))
    )
    (net (code "238") (name "unconnected-(U7-Pad38)") (class "Default")
      (node (ref "U7") (pin "38") (pinfunction "38_38") (pintype "bidirectional"))
    )
    (net (code "239") (name "unconnected-(U7-Pad39)") (class "Default")
      (node (ref "U7") (pin "39") (pinfunction "39_39") (pintype "bidirectional"))
    )
    (net (code "240") (name "unconnected-(U7-Pad40)") (class "Default")
      (node (ref "U7") (pin "40") (pinfunction "40_40") (pintype "input"))
    )
    (net (code "241") (name "unconnected-(U7-Pad41)") (class "Default")
      (node (ref "U7") (pin "41") (pinfunction "41_41") (pintype "bidirectional"))
    )
    (net (code "242") (name "unconnected-(U7-Pad44)") (class "Default")
      (node (ref "U7") (pin "44") (pinfunction "44_44") (pintype "bidirectional"))
    )
    (net (code "243") (name "unconnected-(U7-Pad48)") (class "Default")
      (node (ref "U7") (pin "48") (pinfunction "48_48") (pintype "bidirectional"))
    )
    (net (code "244") (name "unconnected-(U7-Pad50)") (class "Default")
      (node (ref "U7") (pin "50") (pinfunction "50_50") (pintype "bidirectional"))
    )
    (net (code "245") (name "unconnected-(U7-Pad51)") (class "Default")
      (node (ref "U7") (pin "51") (pinfunction "51_51") (pintype "bidirectional"))
    )
    (net (code "246") (name "unconnected-(U7-Pad59)") (class "Default")
      (node (ref "U7") (pin "59") (pinfunction "59_59") (pintype "bidirectional"))
    )
    (net (code "247") (name "unconnected-(U7-Pad60)") (class "Default")
      (node (ref "U7") (pin "60") (pinfunction "60_60") (pintype "bidirectional"))
    )
    (net (code "248") (name "unconnected-(U7-Pad61)") (class "Default")
      (node (ref "U7") (pin "61") (pinfunction "61_61") (pintype "bidirectional"))
    )
    (net (code "249") (name "unconnected-(U8-NC1-Pad6)") (class "Default")
      (node (ref "U8") (pin "6") (pinfunction "NC1_6") (pintype "no_connect"))
    )
    (net (code "250") (name "unconnected-(U8-NC2-Pad9)") (class "Default")
      (node (ref "U8") (pin "9") (pinfunction "NC2_9") (pintype "no_connect"))
    )
    (net (code "251") (name "unconnected-(U10-CLKOUT-Pad22)") (class "Default")
      (node (ref "U10") (pin "22") (pinfunction "CLKOUT_22") (pintype "output"))
    )
    (net (code "252") (name "unconnected-(U10-P3.3-Pad30)") (class "Default")
      (node (ref "U10") (pin "30") (pinfunction "P3.3_30") (pintype "bidirectional"))
    )
    (net (code "253") (name "unconnected-(U10-P3.4-Pad29)") (class "Default")
      (node (ref "U10") (pin "29") (pinfunction "P3.4_29") (pintype "bidirectional"))
    )
    (net (code "254") (name "unconnected-(U10-X2-Pad26)") (class "Default")
      (node (ref "U10") (pin "26") (pinfunction "X2_26") (pintype "input"))
    )
    (net (code "255") (name "unconnected-(U11-NC-Pad2)") (class "Default")
      (node (ref "U11") (pin "2") (pinfunction "NC_2") (pintype "no_connect"))
    )
    (net (code "256") (name "unconnected-(X1-DAT1-Pad8)") (class "Default")
      (node (ref "X1") (pin "8") (pinfunction "DAT1_8") (pintype "bidirectional"))
    )
    (net (code "257") (name "unconnected-(X1-DAT2-Pad1)") (class "Default")
      (node (ref "X1") (pin "1") (pinfunction "DAT2_1") (pintype "bidirectional"))
    )
    (net (code "258") (name "unconnected-(X1-PadB)") (class "Default")
      (node (ref "X1") (pin "B") (pinfunction "B_B") (pintype "bidirectional"))
    )
  )
)
